# stm_v0_7.net
KiCad netlist of a schematic drawn in EAGLE
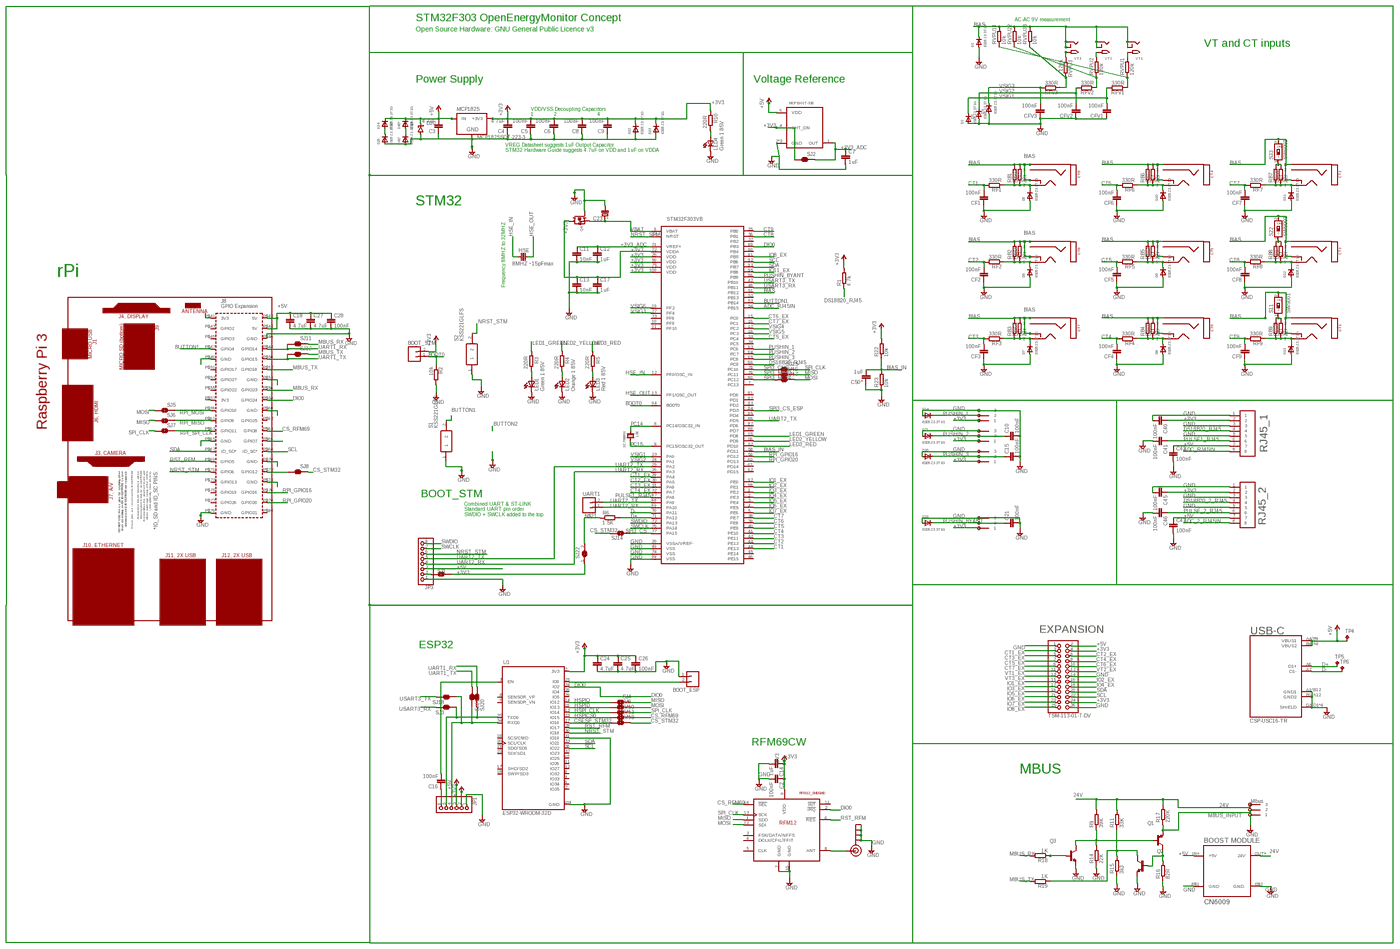
[diagram p0: schematic, sheet 1, overview]
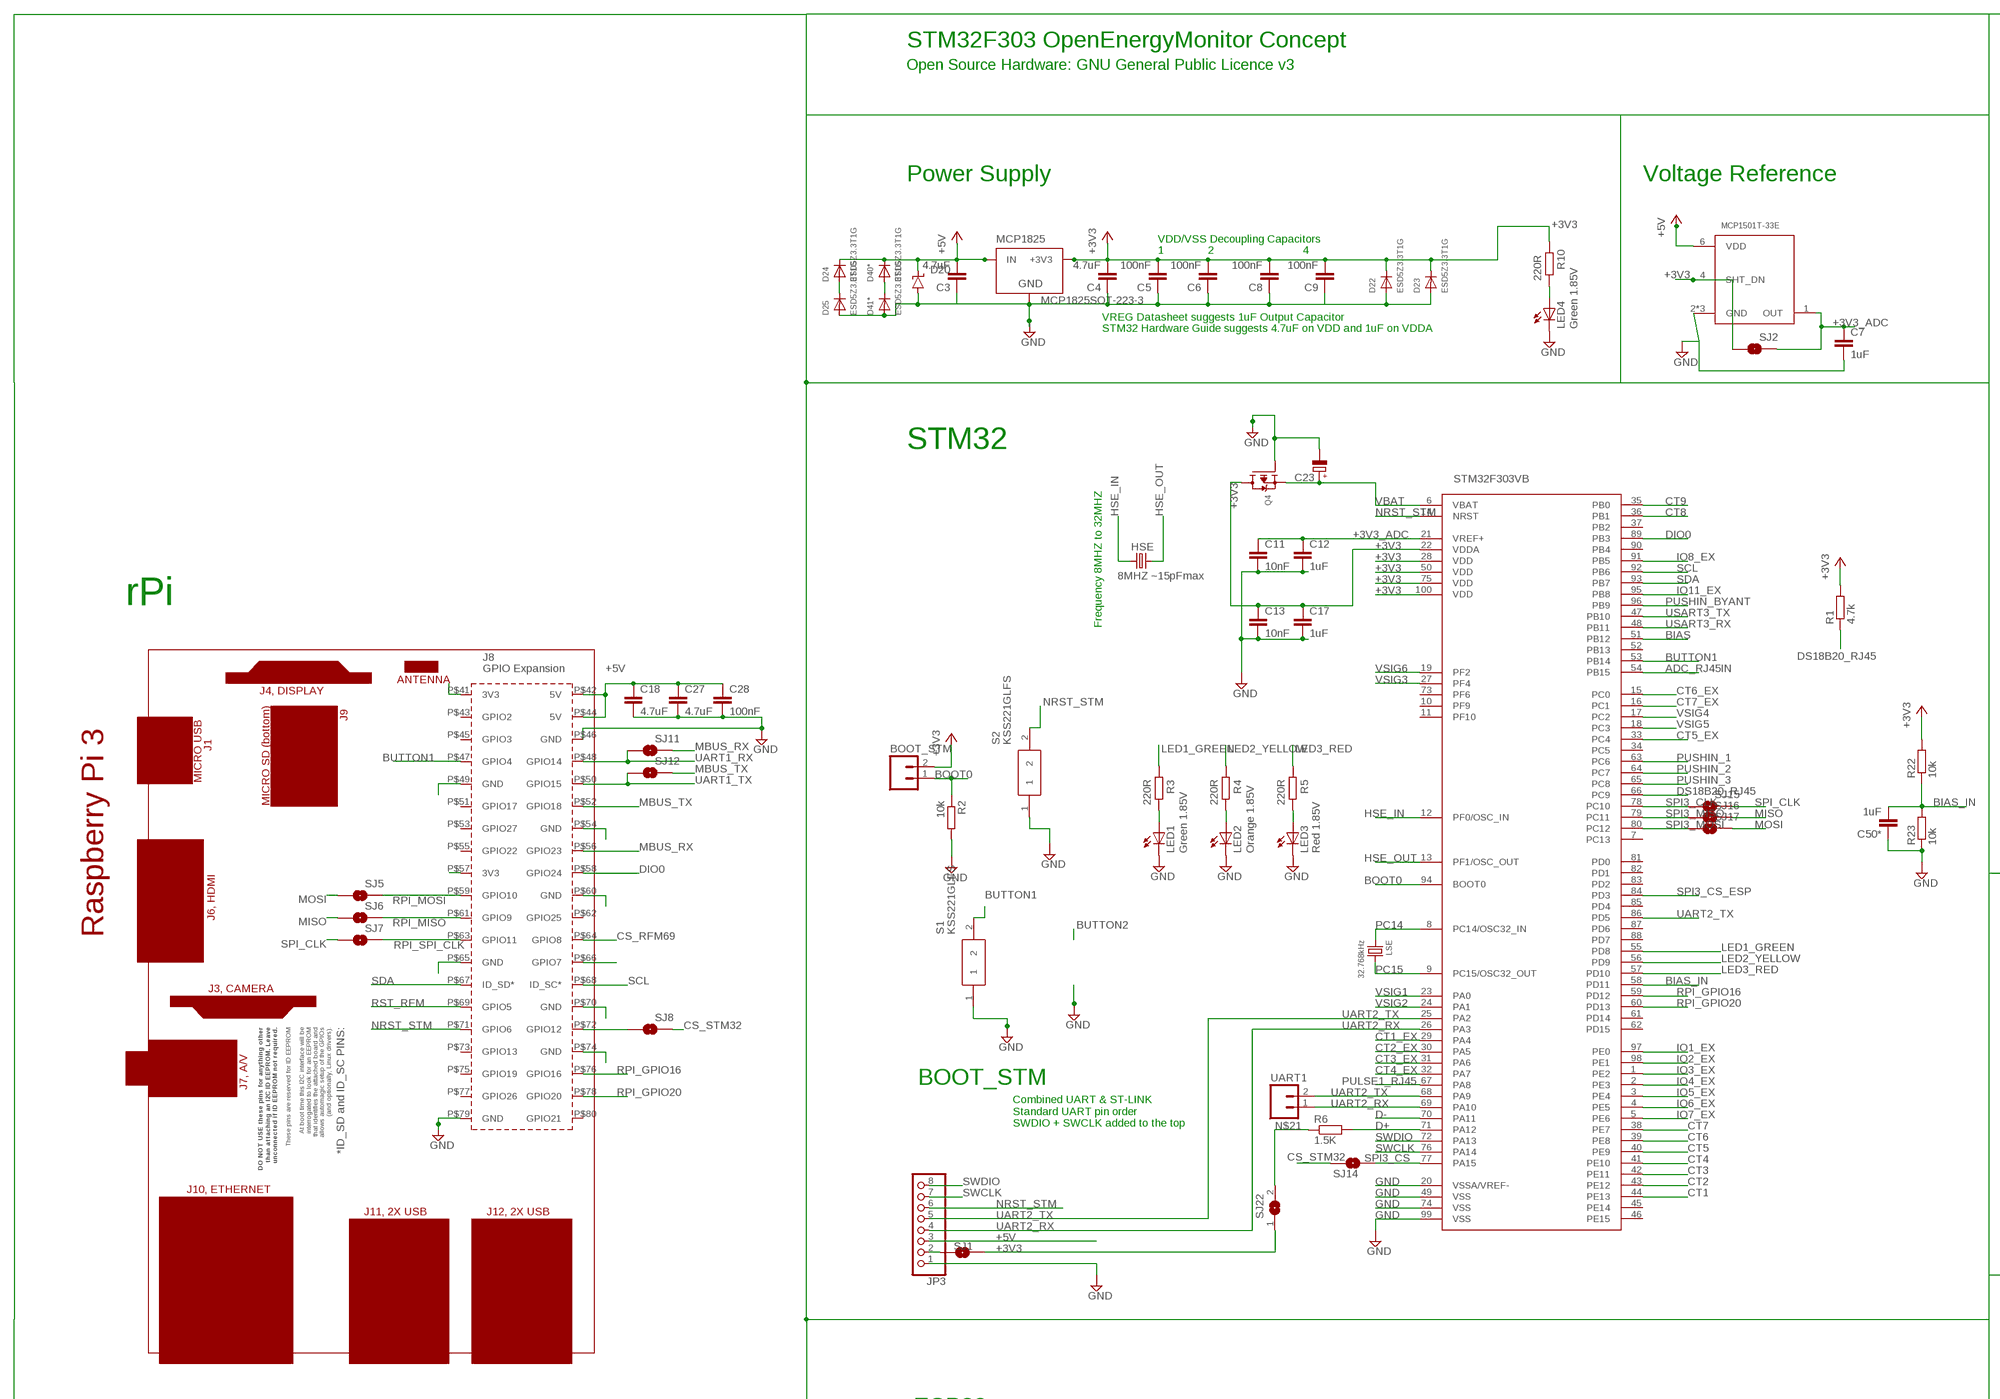
[diagram p1: schematic, sheet 1, part 1 of 4]
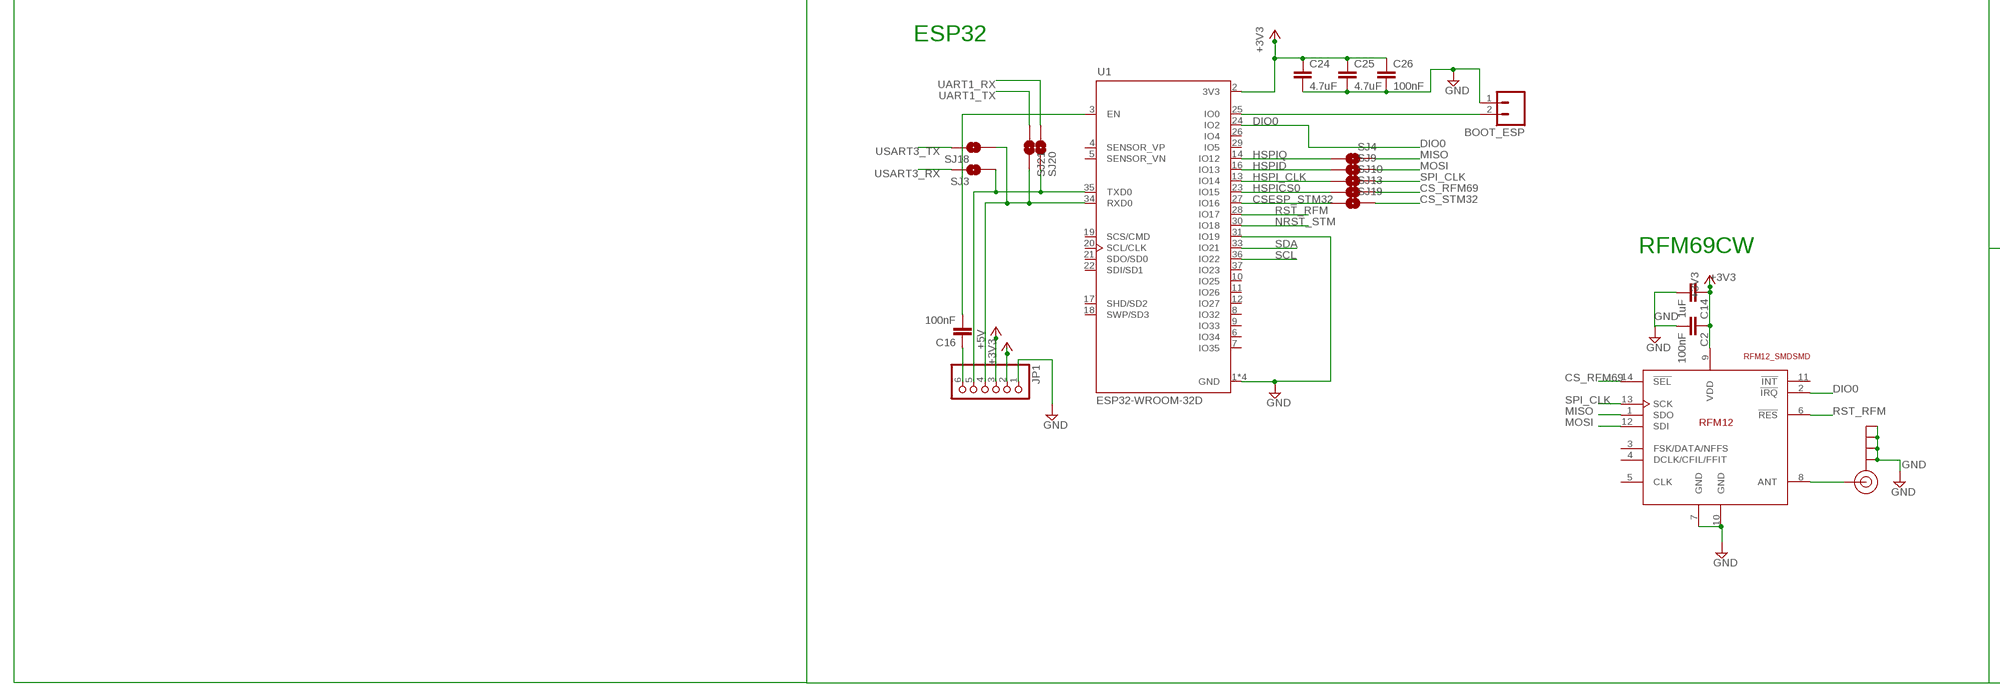
[diagram p2: schematic, sheet 1, part 2 of 4]
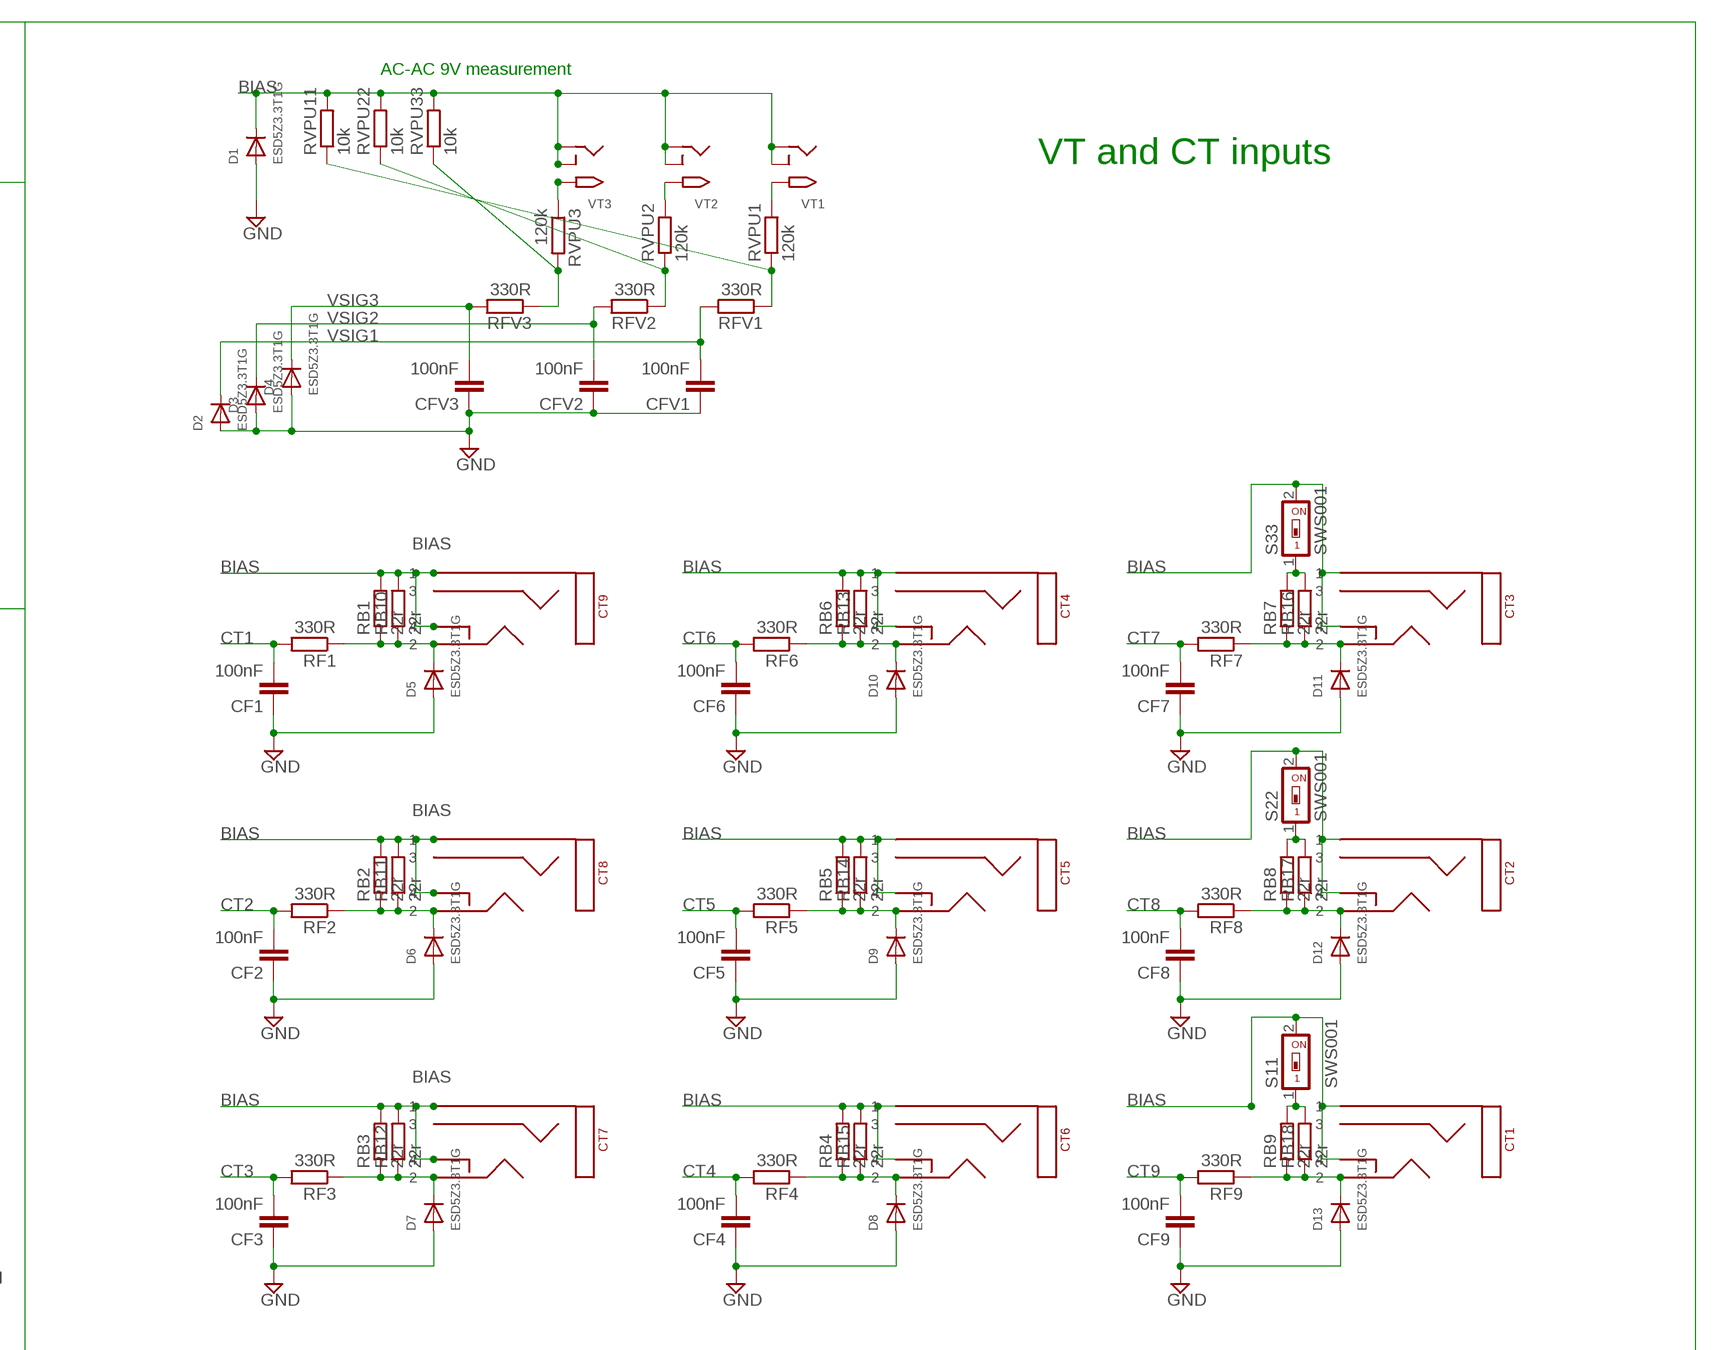
[diagram p3: schematic, sheet 1, part 3 of 4]
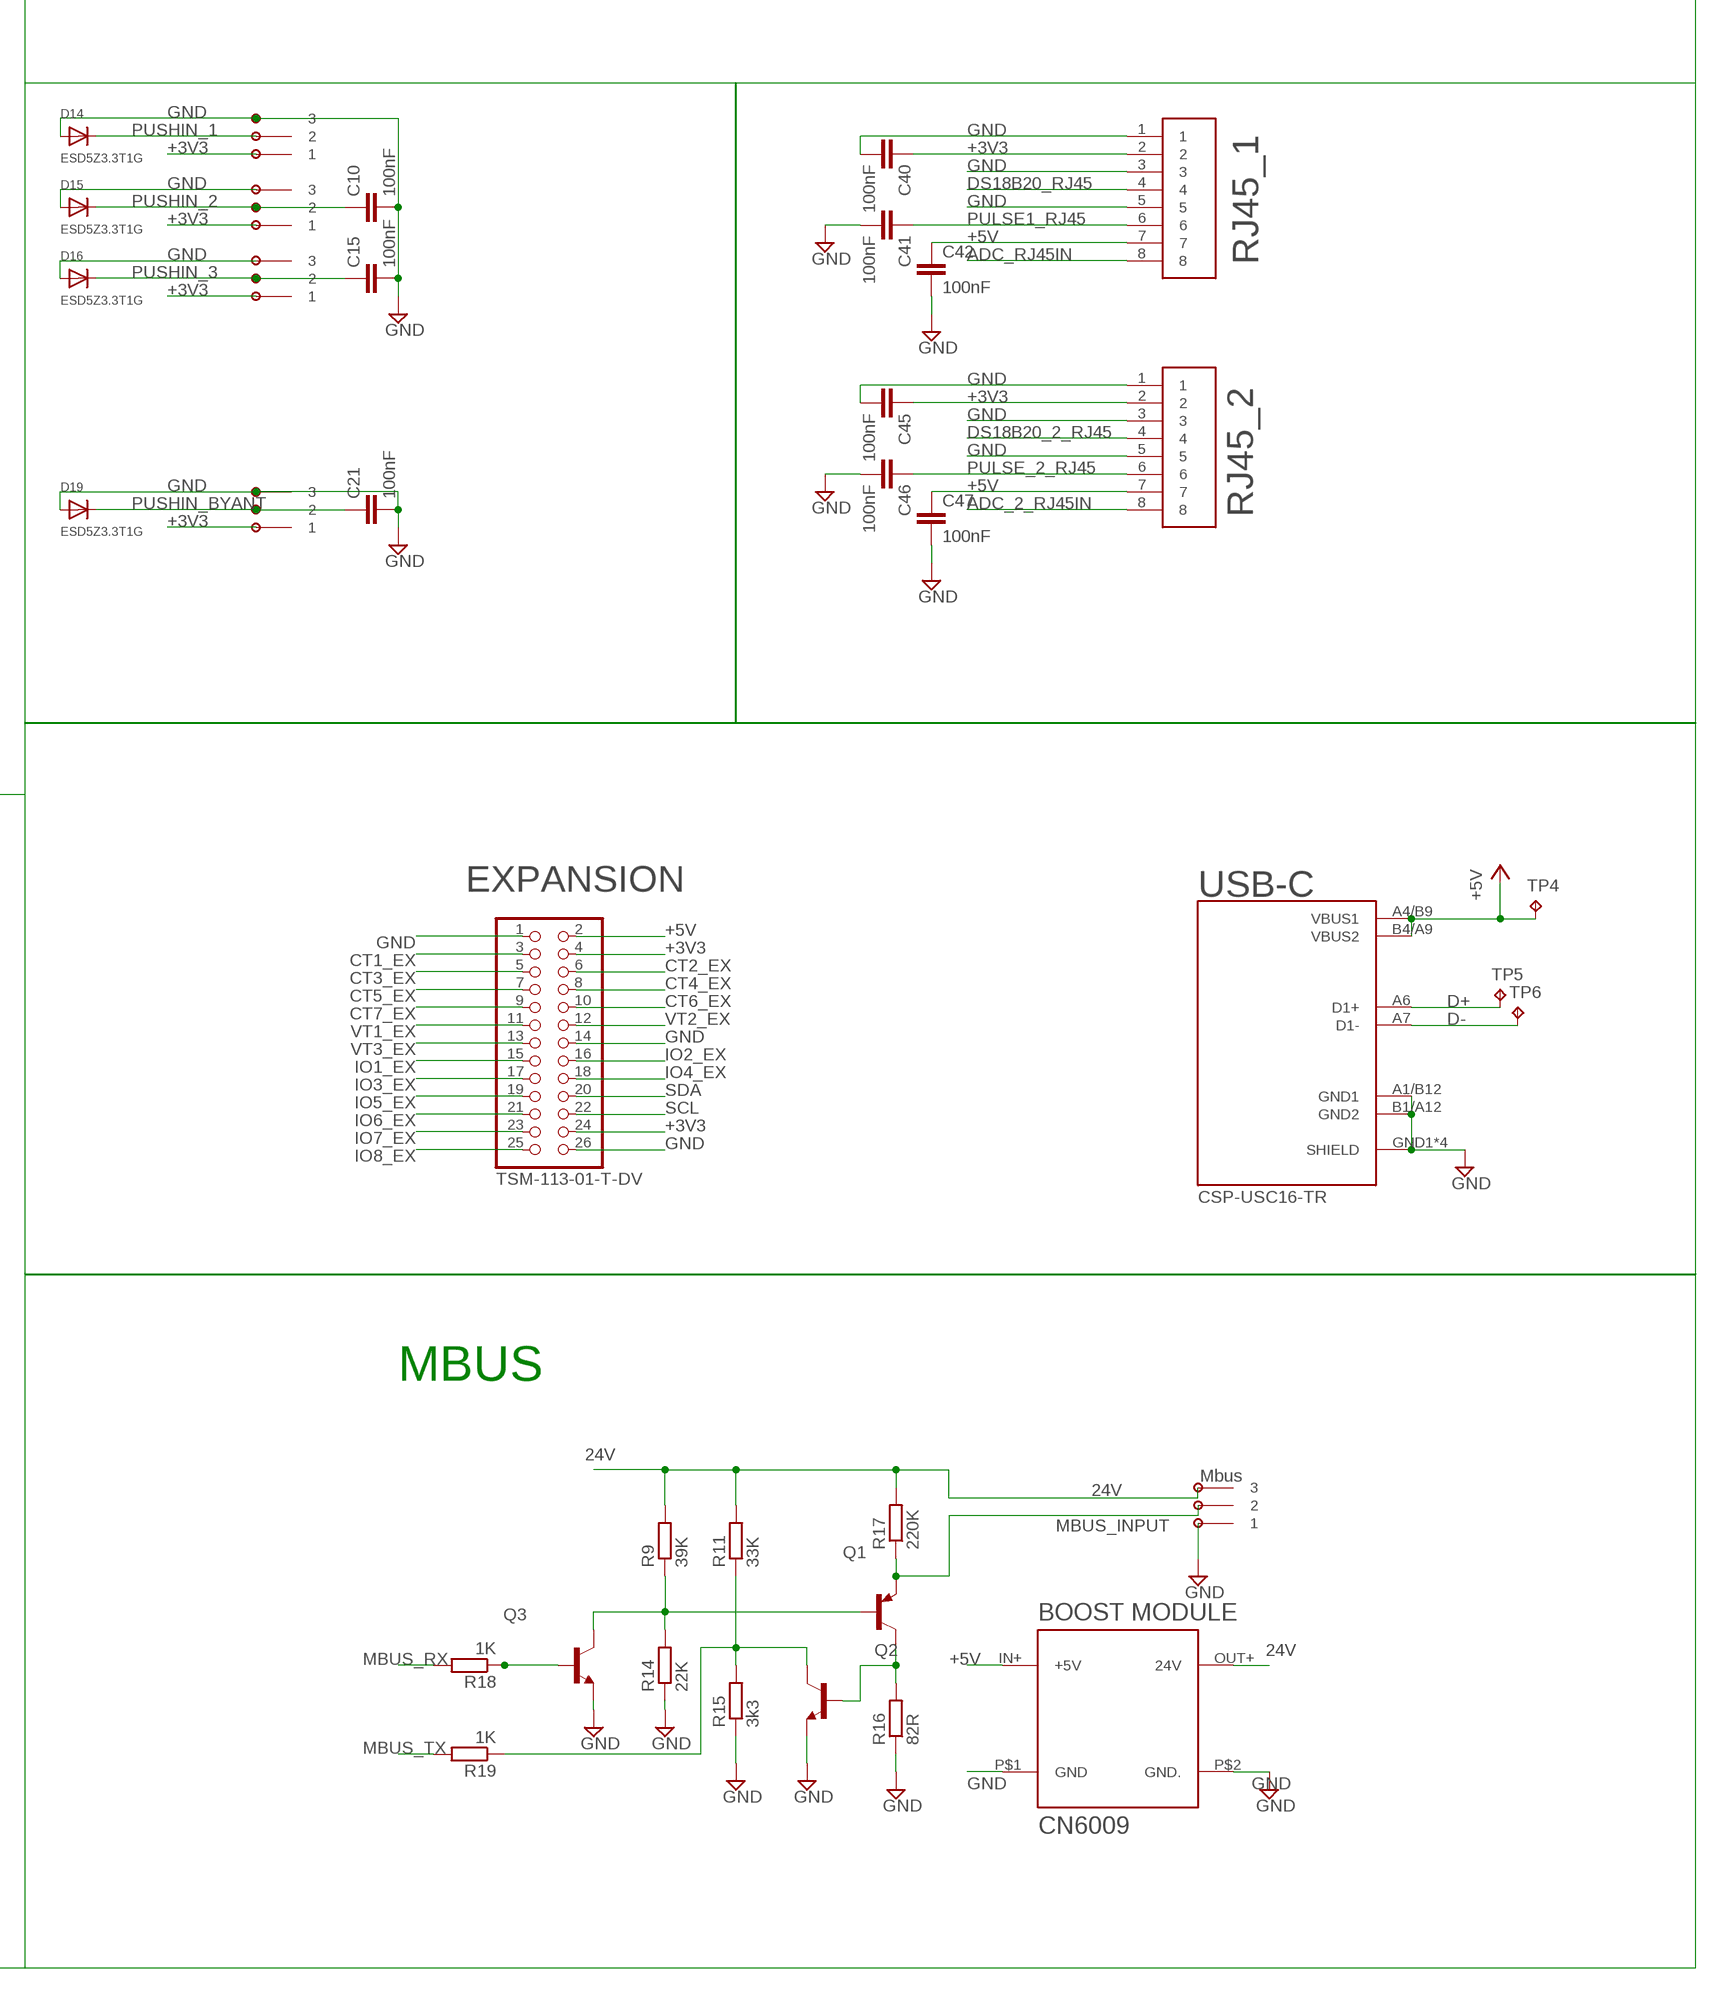
[diagram p4: schematic, sheet 1, part 4 of 4]

(export (version "E")
  (design (tool "Eeschema 10.0.6"))
  (components
    (comp (ref "3POLE_1")
      (value "OMNIMATE_LSF_3COMBICON_SMT_3")
      (footprint "eagle-import:OMNIMATE_LSF_3_SMT")
      (libsource (lib "eagle-import") (part "OMNIMATE_LSF_3COMBICON_SMT_3"))
    )
    (comp (ref "3POLE_2")
      (value "OMNIMATE_LSF_3COMBICON_SMT_3")
      (footprint "eagle-import:OMNIMATE_LSF_3_SMT")
      (libsource (lib "eagle-import") (part "OMNIMATE_LSF_3COMBICON_SMT_3"))
    )
    (comp (ref "3POLE_3")
      (value "OMNIMATE_LSF_3COMBICON_SMT_3")
      (footprint "eagle-import:OMNIMATE_LSF_3_SMT")
      (libsource (lib "eagle-import") (part "OMNIMATE_LSF_3COMBICON_SMT_3"))
    )
    (comp (ref "3POLE_6")
      (value "OMNIMATE_LSF_3COMBICON_SMT_3")
      (footprint "eagle-import:OMNIMATE_LSF_3_SMT")
      (libsource (lib "eagle-import") (part "OMNIMATE_LSF_3COMBICON_SMT_3"))
    )
    (comp (ref "3POLE_7")
      (value "OMNIMATE_LSF_3COMBICON_SMT_3")
      (footprint "eagle-import:OMNIMATE_LSF_3_SMT")
      (libsource (lib "eagle-import") (part "OMNIMATE_LSF_3COMBICON_SMT_3"))
    )
    (comp (ref "BOOT_ESP")
      (value "M02PTH")
      (footprint "eagle-import:1X02")
      (libsource (lib "eagle-import") (part "M02PTH"))
    )
    (comp (ref "BOOT_STM")
      (value "M02PTH")
      (footprint "eagle-import:1X02")
      (libsource (lib "eagle-import") (part "M02PTH"))
    )
    (comp (ref "C2")
      (value "100nF")
      (footprint "eagle-import:C0603")
      (libsource (lib "eagle-import") (part "resistor_C-EUC0603"))
    )
    (comp (ref "C3")
      (value "4.7uF")
      (footprint "eagle-import:C0805")
      (libsource (lib "eagle-import") (part "C-EUC0805"))
    )
    (comp (ref "C4")
      (value "4.7uF")
      (footprint "eagle-import:C0805")
      (libsource (lib "eagle-import") (part "C-EUC0805"))
    )
    (comp (ref "C5")
      (value "100nF")
      (footprint "eagle-import:C0603")
      (libsource (lib "eagle-import") (part "resistor_C-EUC0603"))
    )
    (comp (ref "C6")
      (value "100nF")
      (footprint "eagle-import:C0603")
      (libsource (lib "eagle-import") (part "resistor_C-EUC0603"))
    )
    (comp (ref "C7")
      (value "1uF")
      (footprint "eagle-import:C0805")
      (libsource (lib "eagle-import") (part "C-EUC0805"))
    )
    (comp (ref "C8")
      (value "100nF")
      (footprint "eagle-import:C0603")
      (libsource (lib "eagle-import") (part "resistor_C-EUC0603"))
    )
    (comp (ref "C9")
      (value "100nF")
      (footprint "eagle-import:C0603")
      (libsource (lib "eagle-import") (part "resistor_C-EUC0603"))
    )
    (comp (ref "C10")
      (value "100nF")
      (footprint "eagle-import:C0603")
      (libsource (lib "eagle-import") (part "resistor_C-EUC0603"))
    )
    (comp (ref "C11")
      (value "10nF")
      (footprint "eagle-import:C0603")
      (libsource (lib "eagle-import") (part "C-EUC0603"))
    )
    (comp (ref "C12")
      (value "1uF")
      (footprint "eagle-import:C0805")
      (libsource (lib "eagle-import") (part "C-EUC0805"))
    )
    (comp (ref "C13")
      (value "10nF")
      (footprint "eagle-import:C0603")
      (libsource (lib "eagle-import") (part "C-EUC0603"))
    )
    (comp (ref "C14")
      (value "1uF")
      (footprint "eagle-import:C0805")
      (libsource (lib "eagle-import") (part "C-EUC0805"))
    )
    (comp (ref "C15")
      (value "100nF")
      (footprint "eagle-import:C0603")
      (libsource (lib "eagle-import") (part "resistor_C-EUC0603"))
    )
    (comp (ref "C16")
      (value "100nF")
      (footprint "eagle-import:C0603")
      (libsource (lib "eagle-import") (part "resistor_C-EUC0603"))
    )
    (comp (ref "C17")
      (value "1uF")
      (footprint "eagle-import:C0805")
      (libsource (lib "eagle-import") (part "C-EUC0805"))
    )
    (comp (ref "C18")
      (value "4.7uF")
      (footprint "eagle-import:C0805")
      (libsource (lib "eagle-import") (part "C-EUC0805"))
    )
    (comp (ref "C21")
      (value "100nF")
      (footprint "eagle-import:C0603")
      (libsource (lib "eagle-import") (part "resistor_C-EUC0603"))
    )
    (comp (ref "C23")
      (value "CPOL-EU153CLV-1010")
      (footprint "eagle-import:153CLV-1010")
      (libsource (lib "eagle-import") (part "CPOL-EU153CLV-1010"))
    )
    (comp (ref "C24")
      (value "4.7uF")
      (footprint "eagle-import:C0805")
      (libsource (lib "eagle-import") (part "C-EUC0805"))
    )
    (comp (ref "C25")
      (value "4.7uF")
      (footprint "eagle-import:C0805")
      (libsource (lib "eagle-import") (part "C-EUC0805"))
    )
    (comp (ref "C26")
      (value "100nF")
      (footprint "eagle-import:C0603")
      (libsource (lib "eagle-import") (part "resistor_C-EUC0603"))
    )
    (comp (ref "C27")
      (value "4.7uF")
      (footprint "eagle-import:C0805")
      (libsource (lib "eagle-import") (part "C-EUC0805"))
    )
    (comp (ref "C28")
      (value "100nF")
      (footprint "eagle-import:C0603")
      (libsource (lib "eagle-import") (part "resistor_C-EUC0603"))
    )
    (comp (ref "C40")
      (value "100nF")
      (footprint "eagle-import:C0603")
      (libsource (lib "eagle-import") (part "resistor_C-EUC0603"))
    )
    (comp (ref "C41")
      (value "100nF")
      (footprint "eagle-import:C0603")
      (libsource (lib "eagle-import") (part "resistor_C-EUC0603"))
    )
    (comp (ref "C42")
      (value "100nF")
      (footprint "eagle-import:C0603")
      (libsource (lib "eagle-import") (part "resistor_C-EUC0603"))
    )
    (comp (ref "C45")
      (value "100nF")
      (footprint "eagle-import:C0603")
      (libsource (lib "eagle-import") (part "resistor_C-EUC0603"))
    )
    (comp (ref "C46")
      (value "100nF")
      (footprint "eagle-import:C0603")
      (libsource (lib "eagle-import") (part "resistor_C-EUC0603"))
    )
    (comp (ref "C47")
      (value "100nF")
      (footprint "eagle-import:C0603")
      (libsource (lib "eagle-import") (part "resistor_C-EUC0603"))
    )
    (comp (ref "C50*")
      (value "1uF")
      (footprint "eagle-import:C0603")
      (libsource (lib "eagle-import") (part "C-EUC0603"))
    )
    (comp (ref "CF1")
      (value "100nF")
      (footprint "eagle-import:C0603")
      (libsource (lib "eagle-import") (part "resistor_C-EUC0603"))
    )
    (comp (ref "CF2")
      (value "100nF")
      (footprint "eagle-import:C0603")
      (libsource (lib "eagle-import") (part "resistor_C-EUC0603"))
    )
    (comp (ref "CF3")
      (value "100nF")
      (footprint "eagle-import:C0603")
      (libsource (lib "eagle-import") (part "resistor_C-EUC0603"))
    )
    (comp (ref "CF4")
      (value "100nF")
      (footprint "eagle-import:C0603")
      (libsource (lib "eagle-import") (part "resistor_C-EUC0603"))
    )
    (comp (ref "CF5")
      (value "100nF")
      (footprint "eagle-import:C0603")
      (libsource (lib "eagle-import") (part "resistor_C-EUC0603"))
    )
    (comp (ref "CF6")
      (value "100nF")
      (footprint "eagle-import:C0603")
      (libsource (lib "eagle-import") (part "resistor_C-EUC0603"))
    )
    (comp (ref "CF7")
      (value "100nF")
      (footprint "eagle-import:C0603")
      (libsource (lib "eagle-import") (part "resistor_C-EUC0603"))
    )
    (comp (ref "CF8")
      (value "100nF")
      (footprint "eagle-import:C0603")
      (libsource (lib "eagle-import") (part "resistor_C-EUC0603"))
    )
    (comp (ref "CF9")
      (value "100nF")
      (footprint "eagle-import:C0603")
      (libsource (lib "eagle-import") (part "resistor_C-EUC0603"))
    )
    (comp (ref "CFV1")
      (value "100nF")
      (footprint "eagle-import:C0603")
      (libsource (lib "eagle-import") (part "resistor_C-EUC0603"))
    )
    (comp (ref "CFV2")
      (value "100nF")
      (footprint "eagle-import:C0603")
      (libsource (lib "eagle-import") (part "resistor_C-EUC0603"))
    )
    (comp (ref "CFV3")
      (value "100nF")
      (footprint "eagle-import:C0603")
      (libsource (lib "eagle-import") (part "resistor_C-EUC0603"))
    )
    (comp (ref "CT1")
      (value "STEREO_SMD")
      (footprint "eagle-import:STEREO_SMT")
      (libsource (lib "eagle-import") (part "STEREO_SMD"))
    )
    (comp (ref "CT2")
      (value "STEREO_SMD")
      (footprint "eagle-import:STEREO_SMT")
      (libsource (lib "eagle-import") (part "STEREO_SMD"))
    )
    (comp (ref "CT3")
      (value "STEREO_SMD")
      (footprint "eagle-import:STEREO_SMT")
      (libsource (lib "eagle-import") (part "STEREO_SMD"))
    )
    (comp (ref "CT4")
      (value "STEREO_SMD")
      (footprint "eagle-import:STEREO_SMT")
      (libsource (lib "eagle-import") (part "STEREO_SMD"))
    )
    (comp (ref "CT5")
      (value "STEREO_SMD")
      (footprint "eagle-import:STEREO_SMT")
      (libsource (lib "eagle-import") (part "STEREO_SMD"))
    )
    (comp (ref "CT6")
      (value "STEREO_SMD")
      (footprint "eagle-import:STEREO_SMT")
      (libsource (lib "eagle-import") (part "STEREO_SMD"))
    )
    (comp (ref "CT7")
      (value "STEREO_SMD")
      (footprint "eagle-import:STEREO_SMT")
      (libsource (lib "eagle-import") (part "STEREO_SMD"))
    )
    (comp (ref "CT8")
      (value "STEREO_SMD")
      (footprint "eagle-import:STEREO_SMT")
      (libsource (lib "eagle-import") (part "STEREO_SMD"))
    )
    (comp (ref "CT9")
      (value "STEREO_SMD")
      (footprint "eagle-import:STEREO_SMT")
      (libsource (lib "eagle-import") (part "STEREO_SMD"))
    )
    (comp (ref "D1")
      (value "ESD5Z3.3T1G")
      (footprint "eagle-import:SOD-523")
      (libsource (lib "eagle-import") (part "DIODESOD-523"))
    )
    (comp (ref "D2")
      (value "ESD5Z3.3T1G")
      (footprint "eagle-import:SOD-523")
      (libsource (lib "eagle-import") (part "DIODESOD-523"))
    )
    (comp (ref "D3")
      (value "ESD5Z3.3T1G")
      (footprint "eagle-import:SOD-523")
      (libsource (lib "eagle-import") (part "DIODESOD-523"))
    )
    (comp (ref "D4")
      (value "ESD5Z3.3T1G")
      (footprint "eagle-import:SOD-523")
      (libsource (lib "eagle-import") (part "DIODESOD-523"))
    )
    (comp (ref "D5")
      (value "ESD5Z3.3T1G")
      (footprint "eagle-import:SOD-523")
      (libsource (lib "eagle-import") (part "DIODESOD-523"))
    )
    (comp (ref "D6")
      (value "ESD5Z3.3T1G")
      (footprint "eagle-import:SOD-523")
      (libsource (lib "eagle-import") (part "DIODESOD-523"))
    )
    (comp (ref "D7")
      (value "ESD5Z3.3T1G")
      (footprint "eagle-import:SOD-523")
      (libsource (lib "eagle-import") (part "DIODESOD-523"))
    )
    (comp (ref "D8")
      (value "ESD5Z3.3T1G")
      (footprint "eagle-import:SOD-523")
      (libsource (lib "eagle-import") (part "DIODESOD-523"))
    )
    (comp (ref "D9")
      (value "ESD5Z3.3T1G")
      (footprint "eagle-import:SOD-523")
      (libsource (lib "eagle-import") (part "DIODESOD-523"))
    )
    (comp (ref "D10")
      (value "ESD5Z3.3T1G")
      (footprint "eagle-import:SOD-523")
      (libsource (lib "eagle-import") (part "DIODESOD-523"))
    )
    (comp (ref "D11")
      (value "ESD5Z3.3T1G")
      (footprint "eagle-import:SOD-523")
      (libsource (lib "eagle-import") (part "DIODESOD-523"))
    )
    (comp (ref "D12")
      (value "ESD5Z3.3T1G")
      (footprint "eagle-import:SOD-523")
      (libsource (lib "eagle-import") (part "DIODESOD-523"))
    )
    (comp (ref "D13")
      (value "ESD5Z3.3T1G")
      (footprint "eagle-import:SOD-523")
      (libsource (lib "eagle-import") (part "DIODESOD-523"))
    )
    (comp (ref "D14")
      (value "ESD5Z3.3T1G")
      (footprint "eagle-import:SOD-523")
      (libsource (lib "eagle-import") (part "DIODESOD-523"))
    )
    (comp (ref "D15")
      (value "ESD5Z3.3T1G")
      (footprint "eagle-import:SOD-523")
      (libsource (lib "eagle-import") (part "DIODESOD-523"))
    )
    (comp (ref "D16")
      (value "ESD5Z3.3T1G")
      (footprint "eagle-import:SOD-523")
      (libsource (lib "eagle-import") (part "DIODESOD-523"))
    )
    (comp (ref "D19")
      (value "ESD5Z3.3T1G")
      (footprint "eagle-import:SOD-523")
      (libsource (lib "eagle-import") (part "DIODESOD-523"))
    )
    (comp (ref "D20")
      (value "SUPPRESSOR-SMBJ")
      (footprint "eagle-import:SMBJ")
      (libsource (lib "eagle-import") (part "SUPPRESSOR-SMBJ"))
    )
    (comp (ref "D22")
      (value "ESD5Z3.3T1G")
      (footprint "eagle-import:SOD-523")
      (libsource (lib "eagle-import") (part "DIODESOD-523"))
    )
    (comp (ref "D23")
      (value "ESD5Z3.3T1G")
      (footprint "eagle-import:SOD-523")
      (libsource (lib "eagle-import") (part "DIODESOD-523"))
    )
    (comp (ref "D24")
      (value "ESD5Z3.3T1G")
      (footprint "eagle-import:SOD-523")
      (libsource (lib "eagle-import") (part "DIODESOD-523"))
    )
    (comp (ref "D25")
      (value "ESD5Z3.3T1G")
      (footprint "eagle-import:SOD-523")
      (libsource (lib "eagle-import") (part "DIODESOD-523"))
    )
    (comp (ref "D40*")
      (value "ESD5Z3.3T1G")
      (footprint "eagle-import:SOD-523")
      (libsource (lib "eagle-import") (part "DIODESOD-523"))
    )
    (comp (ref "D41*")
      (value "ESD5Z3.3T1G")
      (footprint "eagle-import:SOD-523")
      (libsource (lib "eagle-import") (part "DIODESOD-523"))
    )
    (comp (ref "EXPANSION")
      (value "TSM-113-01-T-DV")
      (footprint "eagle-import:2X13_SMT")
      (libsource (lib "eagle-import") (part "PINHD-2X13SMT"))
    )
    (comp (ref "HSE")
      (value "8MHZ ~15pFmax")
      (footprint "eagle-import:CTS406")
      (libsource (lib "eagle-import") (part "CRYSTALCTS406"))
    )
    (comp (ref "J$1")
      (value "SMA_EDGE")
      (footprint "eagle-import:SMA-EDGE")
      (libsource (lib "eagle-import") (part "SMA_EDGE"))
    )
    (comp (ref "JP1")
      (value "PINHD-1X61X06_SMT")
      (footprint "eagle-import:1X06_SMT")
      (libsource (lib "eagle-import") (part "PINHD-1X61X06_SMT"))
    )
    (comp (ref "JP3")
      (value "PINHD-1X81X08_SMT")
      (footprint "eagle-import:1X08_SMT")
      (libsource (lib "eagle-import") (part "PINHD-1X81X08_SMT"))
    )
    (comp (ref "LED1")
      (value "Green 1.85V")
      (footprint "eagle-import:CHIP-LED0805")
      (libsource (lib "eagle-import") (part "LEDCHIP-LED0805"))
    )
    (comp (ref "LED2")
      (value "Orange 1.85V")
      (footprint "eagle-import:CHIP-LED0805")
      (libsource (lib "eagle-import") (part "LEDCHIP-LED0805"))
    )
    (comp (ref "LED3")
      (value "Red 1.85V")
      (footprint "eagle-import:CHIP-LED0805")
      (libsource (lib "eagle-import") (part "LEDCHIP-LED0805"))
    )
    (comp (ref "LED4")
      (value "Green 1.85V")
      (footprint "eagle-import:CHIP-LED0805")
      (libsource (lib "eagle-import") (part "LEDCHIP-LED0805"))
    )
    (comp (ref "LSE")
      (value "32.768kHz")
      (footprint "eagle-import:CRYSTAL_8X3.8")
      (libsource (lib "eagle-import") (part "CRYSTAL8X3.8SMT"))
    )
    (comp (ref "MCP1825")
      (value "MCP1825SOT-223-3")
      (footprint "eagle-import:SOT-223")
      (libsource (lib "eagle-import") (part "MCP1825SOT-223-3"))
    )
    (comp (ref "PCB2")
      (value "RPI3YA")
      (footprint "eagle-import:RPI3MIRROR2")
      (libsource (lib "eagle-import") (part "RPI3YA"))
    )
    (comp (ref "Q1")
      (value "MMBT3906")
      (footprint "eagle-import:SOT23")
      (fields
        (field (name "DIGIKEY_PART_NUMBER") "MMBT3906FSCT-ND")
        (field (name "MANUFACTURER") "ON Semiconductor")
        (field (name "CREATED_BY") "PCB Layout")
      )
      (libsource (lib "eagle-import") (part "MMBT3906"))
    )
    (comp (ref "Q2")
      (value "MMBT3904")
      (footprint "eagle-import:SOT23")
      (fields
        (field (name "DIGIKEY_PART_NUMBER") "MMBT3904FSCT-ND")
        (field (name "MANUFACTURER") "ON Semiconductor")
        (field (name "CREATED_BY") "PCB Layout")
      )
      (libsource (lib "eagle-import") (part "MMBT3904"))
    )
    (comp (ref "Q3")
      (value "MMBT3904")
      (footprint "eagle-import:SOT23")
      (fields
        (field (name "DIGIKEY_PART_NUMBER") "MMBT3904FSCT-ND")
        (field (name "MANUFACTURER") "ON Semiconductor")
        (field (name "CREATED_BY") "PCB Layout")
      )
      (libsource (lib "eagle-import") (part "MMBT3904"))
    )
    (comp (ref "Q4")
      (value "MOSFET-P")
      (footprint "eagle-import:SOT23-R")
      (libsource (lib "eagle-import") (part "MOSFET-P"))
    )
    (comp (ref "R1")
      (value "4.7k")
      (footprint "eagle-import:R0603")
      (libsource (lib "eagle-import") (part "resistor_R-EU_R0603"))
    )
    (comp (ref "R2")
      (value "10k")
      (footprint "eagle-import:R0603")
      (libsource (lib "eagle-import") (part "resistor_R-EU_R0603"))
    )
    (comp (ref "R3")
      (value "220R")
      (footprint "eagle-import:R0603")
      (libsource (lib "eagle-import") (part "R-EU_R0603"))
    )
    (comp (ref "R4")
      (value "220R")
      (footprint "eagle-import:R0603")
      (libsource (lib "eagle-import") (part "R-EU_R0603"))
    )
    (comp (ref "R5")
      (value "220R")
      (footprint "eagle-import:R0603")
      (libsource (lib "eagle-import") (part "R-EU_R0603"))
    )
    (comp (ref "R6")
      (value "1.5K")
      (footprint "eagle-import:R0603")
      (libsource (lib "eagle-import") (part "R-EU_R0603"))
    )
    (comp (ref "R9")
      (value "39K")
      (footprint "eagle-import:R0603")
      (libsource (lib "eagle-import") (part "R-EU_R0603"))
    )
    (comp (ref "R10")
      (value "220R")
      (footprint "eagle-import:R0603")
      (libsource (lib "eagle-import") (part "R-EU_R0603"))
    )
    (comp (ref "R11")
      (value "33K")
      (footprint "eagle-import:R0603")
      (libsource (lib "eagle-import") (part "R-EU_R0603"))
    )
    (comp (ref "R14")
      (value "22K")
      (footprint "eagle-import:R0603")
      (libsource (lib "eagle-import") (part "R-EU_R0603"))
    )
    (comp (ref "R15")
      (value "3k3")
      (footprint "eagle-import:R0603")
      (libsource (lib "eagle-import") (part "R-EU_R0603"))
    )
    (comp (ref "R16")
      (value "82R")
      (footprint "eagle-import:R0603")
      (libsource (lib "eagle-import") (part "R-EU_R0603"))
    )
    (comp (ref "R17")
      (value "220K")
      (footprint "eagle-import:R0603")
      (libsource (lib "eagle-import") (part "R-EU_R0603"))
    )
    (comp (ref "R18")
      (value "1K")
      (footprint "eagle-import:R0603")
      (libsource (lib "eagle-import") (part "R-EU_R0603"))
    )
    (comp (ref "R19")
      (value "1K")
      (footprint "eagle-import:R0603")
      (libsource (lib "eagle-import") (part "R-EU_R0603"))
    )
    (comp (ref "R22")
      (value "10k")
      (footprint "eagle-import:R0603")
      (libsource (lib "eagle-import") (part "resistor_R-EU_R0603"))
    )
    (comp (ref "R23")
      (value "10k")
      (footprint "eagle-import:R0603")
      (libsource (lib "eagle-import") (part "resistor_R-EU_R0603"))
    )
    (comp (ref "RB1")
      (value "22r")
      (footprint "eagle-import:R0603")
      (libsource (lib "eagle-import") (part "resistor_R-EU_R0603"))
    )
    (comp (ref "RB2")
      (value "22r")
      (footprint "eagle-import:R0603")
      (libsource (lib "eagle-import") (part "resistor_R-EU_R0603"))
    )
    (comp (ref "RB3")
      (value "22r")
      (footprint "eagle-import:R0603")
      (libsource (lib "eagle-import") (part "resistor_R-EU_R0603"))
    )
    (comp (ref "RB4")
      (value "22r")
      (footprint "eagle-import:R0603")
      (libsource (lib "eagle-import") (part "resistor_R-EU_R0603"))
    )
    (comp (ref "RB5")
      (value "22r")
      (footprint "eagle-import:R0603")
      (libsource (lib "eagle-import") (part "resistor_R-EU_R0603"))
    )
    (comp (ref "RB6")
      (value "22r")
      (footprint "eagle-import:R0603")
      (libsource (lib "eagle-import") (part "resistor_R-EU_R0603"))
    )
    (comp (ref "RB7")
      (value "22r")
      (footprint "eagle-import:R0603")
      (libsource (lib "eagle-import") (part "resistor_R-EU_R0603"))
    )
    (comp (ref "RB8")
      (value "22r")
      (footprint "eagle-import:R0603")
      (libsource (lib "eagle-import") (part "resistor_R-EU_R0603"))
    )
    (comp (ref "RB9")
      (value "22r")
      (footprint "eagle-import:R0603")
      (libsource (lib "eagle-import") (part "resistor_R-EU_R0603"))
    )
    (comp (ref "RB10")
      (value "22r")
      (footprint "eagle-import:0207_7")
      (libsource (lib "eagle-import") (part "R-EU_0207/7"))
    )
    (comp (ref "RB11")
      (value "22r")
      (footprint "eagle-import:0207_7")
      (libsource (lib "eagle-import") (part "R-EU_0207/7"))
    )
    (comp (ref "RB12")
      (value "22r")
      (footprint "eagle-import:0207_7")
      (libsource (lib "eagle-import") (part "R-EU_0207/7"))
    )
    (comp (ref "RB13")
      (value "22r")
      (footprint "eagle-import:0207_7")
      (libsource (lib "eagle-import") (part "R-EU_0207/7"))
    )
    (comp (ref "RB14")
      (value "22r")
      (footprint "eagle-import:0207_7")
      (libsource (lib "eagle-import") (part "R-EU_0207/7"))
    )
    (comp (ref "RB15")
      (value "22r")
      (footprint "eagle-import:0207_7")
      (libsource (lib "eagle-import") (part "R-EU_0207/7"))
    )
    (comp (ref "RB16")
      (value "22r")
      (footprint "eagle-import:0207_7")
      (libsource (lib "eagle-import") (part "R-EU_0207/7"))
    )
    (comp (ref "RB17")
      (value "22r")
      (footprint "eagle-import:0207_7")
      (libsource (lib "eagle-import") (part "R-EU_0207/7"))
    )
    (comp (ref "RB18")
      (value "22r")
      (footprint "eagle-import:0207_7")
      (libsource (lib "eagle-import") (part "R-EU_0207/7"))
    )
    (comp (ref "RF1")
      (value "330R")
      (footprint "eagle-import:R0603")
      (libsource (lib "eagle-import") (part "resistor_R-EU_R0603"))
    )
    (comp (ref "RF2")
      (value "330R")
      (footprint "eagle-import:R0603")
      (libsource (lib "eagle-import") (part "resistor_R-EU_R0603"))
    )
    (comp (ref "RF3")
      (value "330R")
      (footprint "eagle-import:R0603")
      (libsource (lib "eagle-import") (part "resistor_R-EU_R0603"))
    )
    (comp (ref "RF4")
      (value "330R")
      (footprint "eagle-import:R0603")
      (libsource (lib "eagle-import") (part "resistor_R-EU_R0603"))
    )
    (comp (ref "RF5")
      (value "330R")
      (footprint "eagle-import:R0603")
      (libsource (lib "eagle-import") (part "resistor_R-EU_R0603"))
    )
    (comp (ref "RF6")
      (value "330R")
      (footprint "eagle-import:R0603")
      (libsource (lib "eagle-import") (part "resistor_R-EU_R0603"))
    )
    (comp (ref "RF7")
      (value "330R")
      (footprint "eagle-import:R0603")
      (libsource (lib "eagle-import") (part "resistor_R-EU_R0603"))
    )
    (comp (ref "RF8")
      (value "330R")
      (footprint "eagle-import:R0603")
      (libsource (lib "eagle-import") (part "resistor_R-EU_R0603"))
    )
    (comp (ref "RF9")
      (value "330R")
      (footprint "eagle-import:R0603")
      (libsource (lib "eagle-import") (part "resistor_R-EU_R0603"))
    )
    (comp (ref "RFM69HCW")
      (value "RFM12_SMDSMD")
      (footprint "eagle-import:RFM12")
      (libsource (lib "eagle-import") (part "RFM12_SMDSMD"))
    )
    (comp (ref "RFV1")
      (value "330R")
      (footprint "eagle-import:R0603")
      (libsource (lib "eagle-import") (part "resistor_R-EU_R0603"))
    )
    (comp (ref "RFV2")
      (value "330R")
      (footprint "eagle-import:R0603")
      (libsource (lib "eagle-import") (part "resistor_R-EU_R0603"))
    )
    (comp (ref "RFV3")
      (value "330R")
      (footprint "eagle-import:R0603")
      (libsource (lib "eagle-import") (part "resistor_R-EU_R0603"))
    )
    (comp (ref "RJ45_1")
      (value "95501-6889")
      (footprint "eagle-import:955016889")
      (fields (field (name "MOUSER_PART_NUMBER") "538-95501-6889") (field (name "RS_PART_NUMBER") "3862738"))
      (libsource (lib "eagle-import") (part "95501-6889"))
    )
    (comp (ref "RJ45_2")
      (value "95501-6889")
      (footprint "eagle-import:955016889")
      (fields (field (name "MOUSER_PART_NUMBER") "538-95501-6889") (field (name "RS_PART_NUMBER") "3862738"))
      (libsource (lib "eagle-import") (part "95501-6889"))
    )
    (comp (ref "RVPU1")
      (value "120k")
      (footprint "eagle-import:R0603")
      (libsource (lib "eagle-import") (part "resistor_R-EU_R0603"))
    )
    (comp (ref "RVPU2")
      (value "120k")
      (footprint "eagle-import:R0603")
      (libsource (lib "eagle-import") (part "resistor_R-EU_R0603"))
    )
    (comp (ref "RVPU3")
      (value "120k")
      (footprint "eagle-import:R0603")
      (libsource (lib "eagle-import") (part "resistor_R-EU_R0603"))
    )
    (comp (ref "RVPU11")
      (value "10k")
      (footprint "eagle-import:R0603")
      (libsource (lib "eagle-import") (part "resistor_R-EU_R0603"))
    )
    (comp (ref "RVPU22")
      (value "10k")
      (footprint "eagle-import:R0603")
      (libsource (lib "eagle-import") (part "resistor_R-EU_R0603"))
    )
    (comp (ref "RVPU33")
      (value "10k")
      (footprint "eagle-import:R0603")
      (libsource (lib "eagle-import") (part "resistor_R-EU_R0603"))
    )
    (comp (ref "S1")
      (value "KSS221GLFS")
      (footprint "eagle-import:KSS")
      (fields (field (name "RS_PART_NUMBER") "7931689P"))
      (libsource (lib "eagle-import") (part "KSS221GLFS"))
    )
    (comp (ref "S2")
      (value "KSS221GLFS")
      (footprint "eagle-import:KSS")
      (fields (field (name "RS_PART_NUMBER") "7931689P"))
      (libsource (lib "eagle-import") (part "KSS221GLFS"))
    )
    (comp (ref "S11")
      (value "SWS001")
      (footprint "eagle-import:SMS-001")
      (libsource (lib "eagle-import") (part "SWS001"))
    )
    (comp (ref "S22")
      (value "SWS001")
      (footprint "eagle-import:SMS-001")
      (libsource (lib "eagle-import") (part "SWS001"))
    )
    (comp (ref "S33")
      (value "SWS001")
      (footprint "eagle-import:SMS-001")
      (libsource (lib "eagle-import") (part "SWS001"))
    )
    (comp (ref "SJ1")
      (value "SOLDERJUMPERNO")
      (footprint "eagle-import:SJ_2S-NO")
      (libsource (lib "eagle-import") (part "SOLDERJUMPERNO"))
    )
    (comp (ref "SJ2")
      (value "SOLDERJUMPERNO")
      (footprint "eagle-import:SJ_2S-NO")
      (libsource (lib "eagle-import") (part "SOLDERJUMPERNO"))
    )
    (comp (ref "SJ3")
      (value "SOLDERJUMPERNO")
      (footprint "eagle-import:SJ_2S-NO")
      (libsource (lib "eagle-import") (part "SOLDERJUMPERNO"))
    )
    (comp (ref "SJ4")
      (value "SOLDERJUMPERNO")
      (footprint "eagle-import:SJ_2S-NO")
      (libsource (lib "eagle-import") (part "SOLDERJUMPERNO"))
    )
    (comp (ref "SJ5")
      (value "SOLDERJUMPERNO")
      (footprint "eagle-import:SJ_2S-NO")
      (libsource (lib "eagle-import") (part "SOLDERJUMPERNO"))
    )
    (comp (ref "SJ6")
      (value "SOLDERJUMPERNO")
      (footprint "eagle-import:SJ_2S-NO")
      (libsource (lib "eagle-import") (part "SOLDERJUMPERNO"))
    )
    (comp (ref "SJ7")
      (value "SOLDERJUMPERNO")
      (footprint "eagle-import:SJ_2S-NO")
      (libsource (lib "eagle-import") (part "SOLDERJUMPERNO"))
    )
    (comp (ref "SJ8")
      (value "SOLDERJUMPERNO")
      (footprint "eagle-import:SJ_2S-NO")
      (libsource (lib "eagle-import") (part "SOLDERJUMPERNO"))
    )
    (comp (ref "SJ9")
      (value "SOLDERJUMPERNO")
      (footprint "eagle-import:SJ_2S-NO")
      (libsource (lib "eagle-import") (part "SOLDERJUMPERNO"))
    )
    (comp (ref "SJ10")
      (value "SOLDERJUMPERNO")
      (footprint "eagle-import:SJ_2S-NO")
      (libsource (lib "eagle-import") (part "SOLDERJUMPERNO"))
    )
    (comp (ref "SJ11")
      (value "SOLDERJUMPERNO")
      (footprint "eagle-import:SJ_2S-NO")
      (libsource (lib "eagle-import") (part "SOLDERJUMPERNO"))
    )
    (comp (ref "SJ12")
      (value "SOLDERJUMPERNO")
      (footprint "eagle-import:SJ_2S-NO")
      (libsource (lib "eagle-import") (part "SOLDERJUMPERNO"))
    )
    (comp (ref "SJ13")
      (value "SOLDERJUMPERNO")
      (footprint "eagle-import:SJ_2S-NO")
      (libsource (lib "eagle-import") (part "SOLDERJUMPERNO"))
    )
    (comp (ref "SJ14")
      (value "SOLDERJUMPERNO")
      (footprint "eagle-import:SJ_2S-NO")
      (libsource (lib "eagle-import") (part "SOLDERJUMPERNO"))
    )
    (comp (ref "SJ15")
      (value "SOLDERJUMPERNO")
      (footprint "eagle-import:SJ_2S-NO")
      (libsource (lib "eagle-import") (part "SOLDERJUMPERNO"))
    )
    (comp (ref "SJ16")
      (value "SOLDERJUMPERNO")
      (footprint "eagle-import:SJ_2S-NO")
      (libsource (lib "eagle-import") (part "SOLDERJUMPERNO"))
    )
    (comp (ref "SJ17")
      (value "SOLDERJUMPERNO")
      (footprint "eagle-import:SJ_2S-NO")
      (libsource (lib "eagle-import") (part "SOLDERJUMPERNO"))
    )
    (comp (ref "SJ18")
      (value "SOLDERJUMPERNO")
      (footprint "eagle-import:SJ_2S-NO")
      (libsource (lib "eagle-import") (part "SOLDERJUMPERNO"))
    )
    (comp (ref "SJ19")
      (value "SOLDERJUMPERNO")
      (footprint "eagle-import:SJ_2S-NO")
      (libsource (lib "eagle-import") (part "SOLDERJUMPERNO"))
    )
    (comp (ref "SJ20")
      (value "SOLDERJUMPERNO")
      (footprint "eagle-import:SJ_2S-NO")
      (libsource (lib "eagle-import") (part "SOLDERJUMPERNO"))
    )
    (comp (ref "SJ21")
      (value "SOLDERJUMPERNO")
      (footprint "eagle-import:SJ_2S-NO")
      (libsource (lib "eagle-import") (part "SOLDERJUMPERNO"))
    )
    (comp (ref "SJ22")
      (value "SJ-CONCON")
      (footprint "eagle-import:SJ-CON")
      (libsource (lib "eagle-import") (part "SJ-CONCON"))
    )
    (comp (ref "STM32F303VB")
      (value "STM32F303XB")
      (footprint "eagle-import:TQFP100")
      (libsource (lib "eagle-import") (part "STM32F303XB"))
    )
    (comp (ref "TP4")
      (value "TPB1,27")
      (footprint "eagle-import:B1,27")
      (libsource (lib "eagle-import") (part "TPB1,27"))
    )
    (comp (ref "TP5")
      (value "TPB1,27")
      (footprint "eagle-import:B1,27")
      (libsource (lib "eagle-import") (part "TPB1,27"))
    )
    (comp (ref "TP6")
      (value "TPB1,27")
      (footprint "eagle-import:B1,27")
      (libsource (lib "eagle-import") (part "TPB1,27"))
    )
    (comp (ref "U$2")
      (value "BOOST_MODULE")
      (footprint "eagle-import:BOOST")
      (libsource (lib "eagle-import") (part "BOOST_MODULE"))
    )
    (comp (ref "U1")
      (value "ESP32-WROOM-32D")
      (footprint "eagle-import:MODULE_ESP32-WROOM-32D")
      (fields (field (name "MF") "Espressif Systems"))
      (libsource (lib "eagle-import") (part "ESP32-WROOM-32D"))
    )
    (comp (ref "UART1")
      (value "M02PTH")
      (footprint "eagle-import:1X02")
      (libsource (lib "eagle-import") (part "M02PTH"))
    )
    (comp (ref "USB-C")
      (value "CSP-USC16-TR")
      (footprint "eagle-import:USB-C")
      (libsource (lib "eagle-import") (part "CSP-USC16-TR"))
    )
    (comp (ref "VREF_3V3")
      (value "MCP1501T-33E")
      (footprint "eagle-import:SOT95P280X145-6N")
      (libsource (lib "eagle-import") (part "MCP1501T-33E"))
    )
    (comp (ref "VT1")
      (value "2.1MMJACKSMT")
      (footprint "eagle-import:DCJACK_2MM_SMT")
      (libsource (lib "eagle-import") (part "2.1MMJACKSMT"))
    )
    (comp (ref "VT2")
      (value "2.1MMJACKSMT")
      (footprint "eagle-import:DCJACK_2MM_SMT")
      (libsource (lib "eagle-import") (part "2.1MMJACKSMT"))
    )
    (comp (ref "VT3")
      (value "2.1MMJACKSMT")
      (footprint "eagle-import:DCJACK_2MM_SMT")
      (libsource (lib "eagle-import") (part "2.1MMJACKSMT"))
    )
  )
  (nets
    (net (code "1") (name "+3V3") (class "Default")
      (node (ref "3POLE_1") (pin "P$1") (pinfunction "1_P$1") (pintype "bidirectional"))
      (node (ref "3POLE_2") (pin "P$1") (pinfunction "1_P$1") (pintype "bidirectional"))
      (node (ref "3POLE_3") (pin "P$1") (pinfunction "1_P$1") (pintype "bidirectional"))
      (node (ref "3POLE_6") (pin "P$1") (pinfunction "1_P$1") (pintype "bidirectional"))
      (node (ref "BOOT_STM") (pin "2") (pinfunction "2_2") (pintype "passive"))
      (node (ref "C13") (pin "1") (pinfunction "1_1") (pintype "passive"))
      (node (ref "C14") (pin "1") (pinfunction "1_1") (pintype "passive"))
      (node (ref "C17") (pin "1") (pinfunction "1_1") (pintype "passive"))
      (node (ref "C2") (pin "1") (pinfunction "1_1") (pintype "passive"))
      (node (ref "C24") (pin "1") (pinfunction "1_1") (pintype "passive"))
      (node (ref "C25") (pin "1") (pinfunction "1_1") (pintype "passive"))
      (node (ref "C26") (pin "1") (pinfunction "1_1") (pintype "passive"))
      (node (ref "C4") (pin "2") (pinfunction "2_2") (pintype "passive"))
      (node (ref "C40") (pin "1") (pinfunction "1_1") (pintype "passive"))
      (node (ref "C45") (pin "1") (pinfunction "1_1") (pintype "passive"))
      (node (ref "C5") (pin "2") (pinfunction "2_2") (pintype "passive"))
      (node (ref "C6") (pin "2") (pinfunction "2_2") (pintype "passive"))
      (node (ref "C8") (pin "2") (pinfunction "2_2") (pintype "passive"))
      (node (ref "C9") (pin "2") (pinfunction "2_2") (pintype "passive"))
      (node (ref "D22") (pin "K") (pinfunction "C_K") (pintype "passive"))
      (node (ref "D23") (pin "K") (pinfunction "C_K") (pintype "passive"))
      (node (ref "EXPANSION") (pin "24") (pinfunction "24_24") (pintype "passive"))
      (node (ref "EXPANSION") (pin "4") (pinfunction "4_4") (pintype "passive"))
      (node (ref "JP1") (pin "2") (pinfunction "2_2") (pintype "passive"))
      (node (ref "MCP1825") (pin "3") (pinfunction "+3V3_3") (pintype "power_in"))
      (node (ref "Q4") (pin "3") (pinfunction "D_3") (pintype "passive"))
      (node (ref "R1") (pin "2") (pinfunction "2_2") (pintype "passive"))
      (node (ref "R10") (pin "2") (pinfunction "2_2") (pintype "passive"))
      (node (ref "R22") (pin "2") (pinfunction "2_2") (pintype "passive"))
      (node (ref "RFM69HCW") (pin "9") (pinfunction "VDD_9") (pintype "power_in"))
      (node (ref "RJ45_1") (pin "2") (pinfunction "2_2") (pintype "bidirectional"))
      (node (ref "RJ45_2") (pin "2") (pinfunction "2_2") (pintype "bidirectional"))
      (node (ref "SJ1") (pin "2") (pinfunction "2_2") (pintype "passive"))
      (node (ref "SJ2") (pin "1") (pinfunction "1_1") (pintype "passive"))
      (node (ref "SJ22") (pin "1") (pinfunction "1_1") (pintype "passive"))
      (node (ref "STM32F303VB") (pin "100") (pinfunction "VDD_100") (pintype "bidirectional"))
      (node (ref "STM32F303VB") (pin "22") (pinfunction "VDDA_22") (pintype "bidirectional"))
      (node (ref "STM32F303VB") (pin "28") (pinfunction "VDD_28") (pintype "bidirectional"))
      (node (ref "STM32F303VB") (pin "50") (pinfunction "VDD_50") (pintype "bidirectional"))
      (node (ref "STM32F303VB") (pin "75") (pinfunction "VDD_75") (pintype "bidirectional"))
      (node (ref "U1") (pin "2") (pinfunction "3V3_2") (pintype "power_in"))
      (node (ref "VREF_3V3") (pin "4") (pinfunction "SHT_DN_4") (pintype "bidirectional"))
    )
    (net (code "2") (name "+5V") (class "Default")
      (node (ref "C18") (pin "1") (pinfunction "1_1") (pintype "passive"))
      (node (ref "C27") (pin "1") (pinfunction "1_1") (pintype "passive"))
      (node (ref "C28") (pin "1") (pinfunction "1_1") (pintype "passive"))
      (node (ref "C3") (pin "2") (pinfunction "2_2") (pintype "passive"))
      (node (ref "C42") (pin "1") (pinfunction "1_1") (pintype "passive"))
      (node (ref "C47") (pin "1") (pinfunction "1_1") (pintype "passive"))
      (node (ref "D20") (pin "C") (pinfunction "C_C") (pintype "passive"))
      (node (ref "D24") (pin "K") (pinfunction "C_K") (pintype "passive"))
      (node (ref "D40*") (pin "K") (pinfunction "C_K") (pintype "passive"))
      (node (ref "EXPANSION") (pin "2") (pinfunction "2_2") (pintype "passive"))
      (node (ref "JP1") (pin "3") (pinfunction "3_3") (pintype "passive"))
      (node (ref "JP3") (pin "3") (pinfunction "3_3") (pintype "passive"))
      (node (ref "MCP1825") (pin "1") (pinfunction "IN_1") (pintype "power_in"))
      (node (ref "PCB2") (pin "P$42") (pinfunction "5V_P$42") (pintype "bidirectional"))
      (node (ref "PCB2") (pin "P$44") (pinfunction "5V_P$44") (pintype "bidirectional"))
      (node (ref "RJ45_1") (pin "7") (pinfunction "7_7") (pintype "bidirectional"))
      (node (ref "RJ45_2") (pin "7") (pinfunction "7_7") (pintype "bidirectional"))
      (node (ref "TP4") (pin "TP") (pinfunction "TP_TP") (pintype "input"))
      (node (ref "U$2") (pin "IN+") (pinfunction "+5V_IN+") (pintype "bidirectional"))
      (node (ref "USB-C") (pin "A4/B9") (pinfunction "VBUS1_A4/B9") (pintype "passive"))
      (node (ref "USB-C") (pin "B4/A9") (pinfunction "VBUS2_B4/A9") (pintype "passive"))
      (node (ref "VREF_3V3") (pin "6") (pinfunction "VDD_6") (pintype "bidirectional"))
    )
    (net (code "3") (name "/+3V3_ADC") (class "Default")
      (node (ref "C11") (pin "1") (pinfunction "1_1") (pintype "passive"))
      (node (ref "C12") (pin "1") (pinfunction "1_1") (pintype "passive"))
      (node (ref "C7") (pin "1") (pinfunction "1_1") (pintype "passive"))
      (node (ref "SJ2") (pin "2") (pinfunction "2_2") (pintype "passive"))
      (node (ref "STM32F303VB") (pin "21") (pinfunction "VREF+_21") (pintype "bidirectional"))
      (node (ref "VREF_3V3") (pin "1") (pinfunction "OUT_1") (pintype "bidirectional"))
    )
    (net (code "4") (name "/24V") (class "Default")
      (node (ref "3POLE_7") (pin "P$3") (pinfunction "3_P$3") (pintype "bidirectional"))
      (node (ref "R11") (pin "2") (pinfunction "2_2") (pintype "passive"))
      (node (ref "R17") (pin "2") (pinfunction "2_2") (pintype "passive"))
      (node (ref "R9") (pin "2") (pinfunction "2_2") (pintype "passive"))
      (node (ref "U$2") (pin "OUT+") (pinfunction "24V_OUT+") (pintype "bidirectional"))
    )
    (net (code "5") (name "/ADC_2_RJ45IN") (class "Default")
      (node (ref "RJ45_2") (pin "8") (pinfunction "8_8") (pintype "bidirectional"))
    )
    (net (code "6") (name "/ADC_RJ45IN") (class "Default")
      (node (ref "RJ45_1") (pin "8") (pinfunction "8_8") (pintype "bidirectional"))
      (node (ref "STM32F303VB") (pin "54") (pinfunction "PB15_54") (pintype "bidirectional"))
    )
    (net (code "7") (name "/BIAS") (class "Default")
      (node (ref "CT1") (pin "P$1") (pinfunction "1_P$1") (pintype "bidirectional"))
      (node (ref "CT1") (pin "P$4") (pinfunction "4_P$4") (pintype "bidirectional"))
      (node (ref "CT2") (pin "P$1") (pinfunction "1_P$1") (pintype "bidirectional"))
      (node (ref "CT2") (pin "P$4") (pinfunction "4_P$4") (pintype "bidirectional"))
      (node (ref "CT3") (pin "P$1") (pinfunction "1_P$1") (pintype "bidirectional"))
      (node (ref "CT3") (pin "P$4") (pinfunction "4_P$4") (pintype "bidirectional"))
      (node (ref "CT4") (pin "P$1") (pinfunction "1_P$1") (pintype "bidirectional"))
      (node (ref "CT4") (pin "P$4") (pinfunction "4_P$4") (pintype "bidirectional"))
      (node (ref "CT5") (pin "P$1") (pinfunction "1_P$1") (pintype "bidirectional"))
      (node (ref "CT5") (pin "P$4") (pinfunction "4_P$4") (pintype "bidirectional"))
      (node (ref "CT6") (pin "P$1") (pinfunction "1_P$1") (pintype "bidirectional"))
      (node (ref "CT6") (pin "P$4") (pinfunction "4_P$4") (pintype "bidirectional"))
      (node (ref "CT7") (pin "P$1") (pinfunction "1_P$1") (pintype "bidirectional"))
      (node (ref "CT7") (pin "P$4") (pinfunction "4_P$4") (pintype "bidirectional"))
      (node (ref "CT8") (pin "P$1") (pinfunction "1_P$1") (pintype "bidirectional"))
      (node (ref "CT8") (pin "P$4") (pinfunction "4_P$4") (pintype "bidirectional"))
      (node (ref "CT9") (pin "P$1") (pinfunction "1_P$1") (pintype "bidirectional"))
      (node (ref "CT9") (pin "P$4") (pinfunction "4_P$4") (pintype "bidirectional"))
      (node (ref "D1") (pin "K") (pinfunction "C_K") (pintype "passive"))
      (node (ref "RB1") (pin "2") (pinfunction "2_2") (pintype "passive"))
      (node (ref "RB10") (pin "2") (pinfunction "2_2") (pintype "passive"))
      (node (ref "RB11") (pin "2") (pinfunction "2_2") (pintype "passive"))
      (node (ref "RB12") (pin "2") (pinfunction "2_2") (pintype "passive"))
      (node (ref "RB13") (pin "2") (pinfunction "2_2") (pintype "passive"))
      (node (ref "RB14") (pin "2") (pinfunction "2_2") (pintype "passive"))
      (node (ref "RB15") (pin "2") (pinfunction "2_2") (pintype "passive"))
      (node (ref "RB2") (pin "2") (pinfunction "2_2") (pintype "passive"))
      (node (ref "RB3") (pin "2") (pinfunction "2_2") (pintype "passive"))
      (node (ref "RB4") (pin "2") (pinfunction "2_2") (pintype "passive"))
      (node (ref "RB5") (pin "2") (pinfunction "2_2") (pintype "passive"))
      (node (ref "RB6") (pin "2") (pinfunction "2_2") (pintype "passive"))
      (node (ref "RVPU11") (pin "2") (pinfunction "2_2") (pintype "passive"))
      (node (ref "RVPU22") (pin "2") (pinfunction "2_2") (pintype "passive"))
      (node (ref "RVPU33") (pin "2") (pinfunction "2_2") (pintype "passive"))
      (node (ref "S11") (pin "2") (pinfunction "2_2") (pintype "passive"))
      (node (ref "S22") (pin "2") (pinfunction "2_2") (pintype "passive"))
      (node (ref "S33") (pin "2") (pinfunction "2_2") (pintype "passive"))
      (node (ref "STM32F303VB") (pin "51") (pinfunction "PB12_51") (pintype "bidirectional"))
      (node (ref "VT1") (pin "GND") (pinfunction "RING_GND") (pintype "bidirectional"))
      (node (ref "VT1") (pin "GNDBREAK") (pinfunction "RING_SW_GNDBREAK") (pintype "bidirectional"))
      (node (ref "VT2") (pin "GND") (pinfunction "RING_GND") (pintype "bidirectional"))
      (node (ref "VT2") (pin "GNDBREAK") (pinfunction "RING_SW_GNDBREAK") (pintype "bidirectional"))
      (node (ref "VT3") (pin "GND") (pinfunction "RING_GND") (pintype "bidirectional"))
      (node (ref "VT3") (pin "GNDBREAK") (pinfunction "RING_SW_GNDBREAK") (pintype "bidirectional"))
    )
    (net (code "8") (name "/BIAS_IN") (class "Default")
      (node (ref "C50*") (pin "2") (pinfunction "2_2") (pintype "passive"))
      (node (ref "R22") (pin "1") (pinfunction "1_1") (pintype "passive"))
      (node (ref "R23") (pin "2") (pinfunction "2_2") (pintype "passive"))
      (node (ref "STM32F303VB") (pin "58") (pinfunction "PD11_58") (pintype "bidirectional"))
    )
    (net (code "9") (name "/BOOT0") (class "Default")
      (node (ref "BOOT_STM") (pin "1") (pinfunction "1_1") (pintype "passive"))
      (node (ref "R2") (pin "1") (pinfunction "1_1") (pintype "passive"))
      (node (ref "STM32F303VB") (pin "94") (pinfunction "BOOT0_94") (pintype "bidirectional"))
    )
    (net (code "10") (name "/BUTTON1") (class "Default")
      (node (ref "PCB2") (pin "P$47") (pinfunction "GPIO4_P$47") (pintype "bidirectional"))
      (node (ref "S1") (pin "2") (pinfunction "2_2") (pintype "bidirectional"))
      (node (ref "STM32F303VB") (pin "53") (pinfunction "PB14_53") (pintype "bidirectional"))
    )
    (net (code "12") (name "/CSESP_STM32") (class "Default")
      (node (ref "SJ19") (pin "1") (pinfunction "1_1") (pintype "passive"))
      (node (ref "U1") (pin "27") (pinfunction "IO16_27") (pintype "bidirectional"))
    )
    (net (code "13") (name "/CS_RFM69") (class "Default")
      (node (ref "PCB2") (pin "P$64") (pinfunction "GPIO8_P$64") (pintype "bidirectional"))
      (node (ref "RFM69HCW") (pin "14") (pinfunction "~{SEL}_14") (pintype "input"))
      (node (ref "SJ13") (pin "2") (pinfunction "2_2") (pintype "passive"))
    )
    (net (code "14") (name "/CS_STM32") (class "Default")
      (node (ref "SJ14") (pin "1") (pinfunction "1_1") (pintype "passive"))
      (node (ref "SJ19") (pin "2") (pinfunction "2_2") (pintype "passive"))
      (node (ref "SJ8") (pin "2") (pinfunction "2_2") (pintype "passive"))
    )
    (net (code "15") (name "/CT1") (class "Default")
      (node (ref "CF1") (pin "2") (pinfunction "2_2") (pintype "passive"))
      (node (ref "RF1") (pin "2") (pinfunction "2_2") (pintype "passive"))
      (node (ref "STM32F303VB") (pin "44") (pinfunction "PE13_44") (pintype "bidirectional"))
    )
    (net (code "16") (name "/CT1_EX") (class "Default")
      (node (ref "EXPANSION") (pin "3") (pinfunction "3_3") (pintype "passive"))
      (node (ref "STM32F303VB") (pin "29") (pinfunction "PA4_29") (pintype "bidirectional"))
    )
    (net (code "17") (name "/CT2") (class "Default")
      (node (ref "CF2") (pin "2") (pinfunction "2_2") (pintype "passive"))
      (node (ref "RF2") (pin "2") (pinfunction "2_2") (pintype "passive"))
      (node (ref "STM32F303VB") (pin "43") (pinfunction "PE12_43") (pintype "bidirectional"))
    )
    (net (code "18") (name "/CT2_EX") (class "Default")
      (node (ref "EXPANSION") (pin "6") (pinfunction "6_6") (pintype "passive"))
      (node (ref "STM32F303VB") (pin "30") (pinfunction "PA5_30") (pintype "bidirectional"))
    )
    (net (code "19") (name "/CT3") (class "Default")
      (node (ref "CF3") (pin "2") (pinfunction "2_2") (pintype "passive"))
      (node (ref "RF3") (pin "2") (pinfunction "2_2") (pintype "passive"))
      (node (ref "STM32F303VB") (pin "42") (pinfunction "PE11_42") (pintype "bidirectional"))
    )
    (net (code "20") (name "/CT3_EX") (class "Default")
      (node (ref "EXPANSION") (pin "5") (pinfunction "5_5") (pintype "passive"))
      (node (ref "STM32F303VB") (pin "31") (pinfunction "PA6_31") (pintype "bidirectional"))
    )
    (net (code "21") (name "/CT4") (class "Default")
      (node (ref "CF4") (pin "2") (pinfunction "2_2") (pintype "passive"))
      (node (ref "RF4") (pin "2") (pinfunction "2_2") (pintype "passive"))
      (node (ref "STM32F303VB") (pin "41") (pinfunction "PE10_41") (pintype "bidirectional"))
    )
    (net (code "22") (name "/CT4_EX") (class "Default")
      (node (ref "EXPANSION") (pin "8") (pinfunction "8_8") (pintype "passive"))
      (node (ref "STM32F303VB") (pin "32") (pinfunction "PA7_32") (pintype "bidirectional"))
    )
    (net (code "23") (name "/CT5") (class "Default")
      (node (ref "CF5") (pin "2") (pinfunction "2_2") (pintype "passive"))
      (node (ref "RF5") (pin "2") (pinfunction "2_2") (pintype "passive"))
      (node (ref "STM32F303VB") (pin "40") (pinfunction "PE9_40") (pintype "bidirectional"))
    )
    (net (code "24") (name "/CT5_EX") (class "Default")
      (node (ref "EXPANSION") (pin "7") (pinfunction "7_7") (pintype "passive"))
      (node (ref "STM32F303VB") (pin "33") (pinfunction "PC4_33") (pintype "bidirectional"))
    )
    (net (code "25") (name "/CT6") (class "Default")
      (node (ref "CF6") (pin "2") (pinfunction "2_2") (pintype "passive"))
      (node (ref "RF6") (pin "2") (pinfunction "2_2") (pintype "passive"))
      (node (ref "STM32F303VB") (pin "39") (pinfunction "PE8_39") (pintype "bidirectional"))
    )
    (net (code "26") (name "/CT6_EX") (class "Default")
      (node (ref "EXPANSION") (pin "10") (pinfunction "10_10") (pintype "passive"))
      (node (ref "STM32F303VB") (pin "15") (pinfunction "PC0_15") (pintype "bidirectional"))
    )
    (net (code "27") (name "/CT7") (class "Default")
      (node (ref "CF7") (pin "2") (pinfunction "2_2") (pintype "passive"))
      (node (ref "RF7") (pin "2") (pinfunction "2_2") (pintype "passive"))
      (node (ref "STM32F303VB") (pin "38") (pinfunction "PE7_38") (pintype "bidirectional"))
    )
    (net (code "28") (name "/CT7_EX") (class "Default")
      (node (ref "EXPANSION") (pin "9") (pinfunction "9_9") (pintype "passive"))
      (node (ref "STM32F303VB") (pin "16") (pinfunction "PC1_16") (pintype "bidirectional"))
    )
    (net (code "29") (name "/CT8") (class "Default")
      (node (ref "CF8") (pin "2") (pinfunction "2_2") (pintype "passive"))
      (node (ref "RF8") (pin "2") (pinfunction "2_2") (pintype "passive"))
      (node (ref "STM32F303VB") (pin "36") (pinfunction "PB1_36") (pintype "bidirectional"))
    )
    (net (code "30") (name "/CT9") (class "Default")
      (node (ref "CF9") (pin "2") (pinfunction "2_2") (pintype "passive"))
      (node (ref "RF9") (pin "2") (pinfunction "2_2") (pintype "passive"))
      (node (ref "STM32F303VB") (pin "35") (pinfunction "PB0_35") (pintype "bidirectional"))
    )
    (net (code "31") (name "/D+") (class "Default")
      (node (ref "R6") (pin "2") (pinfunction "2_2") (pintype "passive"))
      (node (ref "STM32F303VB") (pin "71") (pinfunction "PA12_71") (pintype "bidirectional"))
      (node (ref "TP5") (pin "TP") (pinfunction "TP_TP") (pintype "input"))
      (node (ref "USB-C") (pin "A6") (pinfunction "D1+_A6") (pintype "passive"))
    )
    (net (code "32") (name "/D-") (class "Default")
      (node (ref "STM32F303VB") (pin "70") (pinfunction "PA11_70") (pintype "bidirectional"))
      (node (ref "TP6") (pin "TP") (pinfunction "TP_TP") (pintype "input"))
      (node (ref "USB-C") (pin "A7") (pinfunction "D1-_A7") (pintype "passive"))
    )
    (net (code "33") (name "/DIO0") (class "Default")
      (node (ref "PCB2") (pin "P$58") (pinfunction "GPIO24_P$58") (pintype "bidirectional"))
      (node (ref "RFM69HCW") (pin "2") (pinfunction "~{IRQ}_2") (pintype "output"))
      (node (ref "STM32F303VB") (pin "89") (pinfunction "PB3_89") (pintype "bidirectional"))
      (node (ref "U1") (pin "24") (pinfunction "IO2_24") (pintype "bidirectional"))
    )
    (net (code "34") (name "/DS18B20_2_RJ45") (class "Default")
      (node (ref "RJ45_2") (pin "4") (pinfunction "4_4") (pintype "bidirectional"))
    )
    (net (code "35") (name "/DS18B20_RJ45") (class "Default")
      (node (ref "R1") (pin "1") (pinfunction "1_1") (pintype "passive"))
      (node (ref "RJ45_1") (pin "4") (pinfunction "4_4") (pintype "bidirectional"))
      (node (ref "STM32F303VB") (pin "66") (pinfunction "PC9_66") (pintype "bidirectional"))
    )
    (net (code "36") (name "/HSE_IN") (class "Default")
      (node (ref "HSE") (pin "1") (pinfunction "1_1") (pintype "passive"))
      (node (ref "STM32F303VB") (pin "12") (pinfunction "PF0/OSC_IN_12") (pintype "bidirectional"))
    )
    (net (code "37") (name "/HSE_OUT") (class "Default")
      (node (ref "HSE") (pin "3") (pinfunction "2_3") (pintype "passive"))
      (node (ref "STM32F303VB") (pin "13") (pinfunction "PF1/OSC_OUT_13") (pintype "bidirectional"))
    )
    (net (code "38") (name "/HSPICS0") (class "Default")
      (node (ref "SJ13") (pin "1") (pinfunction "1_1") (pintype "passive"))
      (node (ref "U1") (pin "23") (pinfunction "IO15_23") (pintype "bidirectional"))
    )
    (net (code "39") (name "/HSPID") (class "Default")
      (node (ref "SJ9") (pin "1") (pinfunction "1_1") (pintype "passive"))
      (node (ref "U1") (pin "16") (pinfunction "IO13_16") (pintype "bidirectional"))
    )
    (net (code "40") (name "/HSPIQ") (class "Default")
      (node (ref "SJ4") (pin "1") (pinfunction "1_1") (pintype "passive"))
      (node (ref "U1") (pin "14") (pinfunction "IO12_14") (pintype "bidirectional"))
    )
    (net (code "41") (name "/HSPI_CLK") (class "Default")
      (node (ref "SJ10") (pin "1") (pinfunction "1_1") (pintype "passive"))
      (node (ref "U1") (pin "13") (pinfunction "IO14_13") (pintype "bidirectional"))
    )
    (net (code "42") (name "/IO1_EX") (class "Default")
      (node (ref "EXPANSION") (pin "15") (pinfunction "15_15") (pintype "passive"))
      (node (ref "STM32F303VB") (pin "97") (pinfunction "PE0_97") (pintype "bidirectional"))
    )
    (net (code "43") (name "/IO2_EX") (class "Default")
      (node (ref "EXPANSION") (pin "16") (pinfunction "16_16") (pintype "passive"))
      (node (ref "STM32F303VB") (pin "98") (pinfunction "PE1_98") (pintype "bidirectional"))
    )
    (net (code "44") (name "/IO3_EX") (class "Default")
      (node (ref "EXPANSION") (pin "17") (pinfunction "17_17") (pintype "passive"))
      (node (ref "STM32F303VB") (pin "1") (pinfunction "PE2_1") (pintype "bidirectional"))
    )
    (net (code "45") (name "/IO4_EX") (class "Default")
      (node (ref "EXPANSION") (pin "18") (pinfunction "18_18") (pintype "passive"))
      (node (ref "STM32F303VB") (pin "2") (pinfunction "PE3_2") (pintype "bidirectional"))
    )
    (net (code "46") (name "/IO5_EX") (class "Default")
      (node (ref "EXPANSION") (pin "19") (pinfunction "19_19") (pintype "passive"))
      (node (ref "STM32F303VB") (pin "3") (pinfunction "PE4_3") (pintype "bidirectional"))
    )
    (net (code "47") (name "/IO6_EX") (class "Default")
      (node (ref "EXPANSION") (pin "21") (pinfunction "21_21") (pintype "passive"))
      (node (ref "STM32F303VB") (pin "4") (pinfunction "PE5_4") (pintype "bidirectional"))
    )
    (net (code "48") (name "/IO7_EX") (class "Default")
      (node (ref "EXPANSION") (pin "23") (pinfunction "23_23") (pintype "passive"))
      (node (ref "STM32F303VB") (pin "5") (pinfunction "PE6_5") (pintype "bidirectional"))
    )
    (net (code "49") (name "/IO8_EX") (class "Default")
      (node (ref "EXPANSION") (pin "25") (pinfunction "25_25") (pintype "passive"))
      (node (ref "STM32F303VB") (pin "91") (pinfunction "PB5_91") (pintype "bidirectional"))
    )
    (net (code "50") (name "/IO11_EX") (class "Default")
      (node (ref "STM32F303VB") (pin "95") (pinfunction "PB8_95") (pintype "bidirectional"))
    )
    (net (code "51") (name "/LED1_GREEN") (class "Default")
      (node (ref "R3") (pin "2") (pinfunction "2_2") (pintype "passive"))
      (node (ref "STM32F303VB") (pin "55") (pinfunction "PD8_55") (pintype "bidirectional"))
    )
    (net (code "52") (name "/LED2_YELLOW") (class "Default")
      (node (ref "R4") (pin "2") (pinfunction "2_2") (pintype "passive"))
      (node (ref "STM32F303VB") (pin "56") (pinfunction "PD9_56") (pintype "bidirectional"))
    )
    (net (code "53") (name "/LED3_RED") (class "Default")
      (node (ref "R5") (pin "2") (pinfunction "2_2") (pintype "passive"))
      (node (ref "STM32F303VB") (pin "57") (pinfunction "PD10_57") (pintype "bidirectional"))
    )
    (net (code "54") (name "/MBUS_INPUT") (class "Default")
      (node (ref "3POLE_7") (pin "P$2") (pinfunction "2_P$2") (pintype "bidirectional"))
      (node (ref "Q1") (pin "2") (pinfunction "E_2") (pintype "passive"))
      (node (ref "R17") (pin "1") (pinfunction "1_1") (pintype "passive"))
    )
    (net (code "55") (name "/MBUS_RX") (class "Default")
      (node (ref "PCB2") (pin "P$56") (pinfunction "GPIO23_P$56") (pintype "bidirectional"))
      (node (ref "R18") (pin "2") (pinfunction "2_2") (pintype "passive"))
      (node (ref "SJ11") (pin "2") (pinfunction "2_2") (pintype "passive"))
    )
    (net (code "56") (name "/MBUS_TX") (class "Default")
      (node (ref "PCB2") (pin "P$52") (pinfunction "GPIO18_P$52") (pintype "bidirectional"))
      (node (ref "R19") (pin "2") (pinfunction "2_2") (pintype "passive"))
      (node (ref "SJ12") (pin "2") (pinfunction "2_2") (pintype "passive"))
    )
    (net (code "57") (name "/MISO") (class "Default")
      (node (ref "RFM69HCW") (pin "1") (pinfunction "SDO_1") (pintype "output"))
      (node (ref "SJ16") (pin "2") (pinfunction "2_2") (pintype "passive"))
      (node (ref "SJ4") (pin "2") (pinfunction "2_2") (pintype "passive"))
      (node (ref "SJ6") (pin "1") (pinfunction "1_1") (pintype "passive"))
    )
    (net (code "58") (name "/MOSI") (class "Default")
      (node (ref "RFM69HCW") (pin "12") (pinfunction "SDI_12") (pintype "input"))
      (node (ref "SJ17") (pin "2") (pinfunction "2_2") (pintype "passive"))
      (node (ref "SJ5") (pin "1") (pinfunction "1_1") (pintype "passive"))
      (node (ref "SJ9") (pin "2") (pinfunction "2_2") (pintype "passive"))
    )
    (net (code "59") (name "/N$21") (class "Default")
      (node (ref "R6") (pin "1") (pinfunction "1_1") (pintype "passive"))
      (node (ref "SJ22") (pin "2") (pinfunction "2_2") (pintype "passive"))
    )
    (net (code "60") (name "/NRST_STM") (class "Default")
      (node (ref "JP3") (pin "6") (pinfunction "6_6") (pintype "passive"))
      (node (ref "PCB2") (pin "P$71") (pinfunction "GPIO6_P$71") (pintype "bidirectional"))
      (node (ref "S2") (pin "2") (pinfunction "2_2") (pintype "bidirectional"))
      (node (ref "STM32F303VB") (pin "14") (pinfunction "NRST_14") (pintype "bidirectional"))
      (node (ref "U1") (pin "30") (pinfunction "IO18_30") (pintype "bidirectional"))
    )
    (net (code "61") (name "/PC14") (class "Default")
      (node (ref "LSE") (pin "P$1") (pinfunction "1_P$1") (pintype "passive"))
      (node (ref "STM32F303VB") (pin "8") (pinfunction "PC14/OSC32_IN_8") (pintype "bidirectional"))
    )
    (net (code "62") (name "/PC15") (class "Default")
      (node (ref "LSE") (pin "P$4") (pinfunction "2_P$4") (pintype "passive"))
      (node (ref "STM32F303VB") (pin "9") (pinfunction "PC15/OSC32_OUT_9") (pintype "bidirectional"))
    )
    (net (code "63") (name "/PULSE1_RJ45") (class "Default")
      (node (ref "C41") (pin "1") (pinfunction "1_1") (pintype "passive"))
      (node (ref "RJ45_1") (pin "6") (pinfunction "6_6") (pintype "bidirectional"))
      (node (ref "STM32F303VB") (pin "67") (pinfunction "PA8_67") (pintype "bidirectional"))
    )
    (net (code "64") (name "/PULSE_2_RJ45") (class "Default")
      (node (ref "C46") (pin "1") (pinfunction "1_1") (pintype "passive"))
      (node (ref "RJ45_2") (pin "6") (pinfunction "6_6") (pintype "bidirectional"))
    )
    (net (code "65") (name "/PUSHIN_1") (class "Default")
      (node (ref "3POLE_1") (pin "P$2") (pinfunction "2_P$2") (pintype "bidirectional"))
      (node (ref "D14") (pin "K") (pinfunction "C_K") (pintype "passive"))
      (node (ref "STM32F303VB") (pin "63") (pinfunction "PC6_63") (pintype "bidirectional"))
    )
    (net (code "66") (name "/PUSHIN_2") (class "Default")
      (node (ref "3POLE_2") (pin "P$2") (pinfunction "2_P$2") (pintype "bidirectional"))
      (node (ref "C10") (pin "1") (pinfunction "1_1") (pintype "passive"))
      (node (ref "D15") (pin "K") (pinfunction "C_K") (pintype "passive"))
      (node (ref "STM32F303VB") (pin "64") (pinfunction "PC7_64") (pintype "bidirectional"))
    )
    (net (code "67") (name "/PUSHIN_3") (class "Default")
      (node (ref "3POLE_3") (pin "P$2") (pinfunction "2_P$2") (pintype "bidirectional"))
      (node (ref "C15") (pin "1") (pinfunction "1_1") (pintype "passive"))
      (node (ref "D16") (pin "K") (pinfunction "C_K") (pintype "passive"))
      (node (ref "STM32F303VB") (pin "65") (pinfunction "PC8_65") (pintype "bidirectional"))
    )
    (net (code "68") (name "/PUSHIN_BYANT") (class "Default")
      (node (ref "3POLE_6") (pin "P$2") (pinfunction "2_P$2") (pintype "bidirectional"))
      (node (ref "C21") (pin "1") (pinfunction "1_1") (pintype "passive"))
      (node (ref "D19") (pin "K") (pinfunction "C_K") (pintype "passive"))
      (node (ref "STM32F303VB") (pin "96") (pinfunction "PB9_96") (pintype "bidirectional"))
    )
    (net (code "69") (name "/RPI_GPIO16") (class "Default")
      (node (ref "PCB2") (pin "P$76") (pinfunction "GPIO16_P$76") (pintype "bidirectional"))
      (node (ref "STM32F303VB") (pin "59") (pinfunction "PD12_59") (pintype "bidirectional"))
    )
    (net (code "70") (name "/RPI_GPIO20") (class "Default")
      (node (ref "PCB2") (pin "P$78") (pinfunction "GPIO20_P$78") (pintype "bidirectional"))
      (node (ref "STM32F303VB") (pin "60") (pinfunction "PD13_60") (pintype "bidirectional"))
    )
    (net (code "71") (name "/RPI_MISO") (class "Default")
      (node (ref "PCB2") (pin "P$61") (pinfunction "GPIO9_P$61") (pintype "bidirectional"))
      (node (ref "SJ6") (pin "2") (pinfunction "2_2") (pintype "passive"))
    )
    (net (code "72") (name "/RPI_MOSI") (class "Default")
      (node (ref "PCB2") (pin "P$59") (pinfunction "GPIO10_P$59") (pintype "bidirectional"))
      (node (ref "SJ5") (pin "2") (pinfunction "2_2") (pintype "passive"))
    )
    (net (code "73") (name "/RPI_SPI_CLK") (class "Default")
      (node (ref "PCB2") (pin "P$63") (pinfunction "GPIO11_P$63") (pintype "bidirectional"))
      (node (ref "SJ7") (pin "2") (pinfunction "2_2") (pintype "passive"))
    )
    (net (code "74") (name "/RST_RFM") (class "Default")
      (node (ref "PCB2") (pin "P$69") (pinfunction "GPIO5_P$69") (pintype "bidirectional"))
      (node (ref "RFM69HCW") (pin "6") (pinfunction "~{RES}_6") (pintype "bidirectional"))
      (node (ref "U1") (pin "28") (pinfunction "IO17_28") (pintype "bidirectional"))
    )
    (net (code "75") (name "/SCL") (class "Default")
      (node (ref "EXPANSION") (pin "22") (pinfunction "22_22") (pintype "passive"))
      (node (ref "PCB2") (pin "P$68") (pinfunction "ID_SC*_P$68") (pintype "bidirectional"))
      (node (ref "STM32F303VB") (pin "92") (pinfunction "PB6_92") (pintype "bidirectional"))
      (node (ref "U1") (pin "36") (pinfunction "IO22_36") (pintype "bidirectional"))
    )
    (net (code "76") (name "/SDA") (class "Default")
      (node (ref "EXPANSION") (pin "20") (pinfunction "20_20") (pintype "passive"))
      (node (ref "PCB2") (pin "P$67") (pinfunction "ID_SD*_P$67") (pintype "bidirectional"))
      (node (ref "STM32F303VB") (pin "93") (pinfunction "PB7_93") (pintype "bidirectional"))
      (node (ref "U1") (pin "33") (pinfunction "IO21_33") (pintype "bidirectional"))
    )
    (net (code "77") (name "/SPI3_CLK") (class "Default")
      (node (ref "SJ15") (pin "1") (pinfunction "1_1") (pintype "passive"))
      (node (ref "STM32F303VB") (pin "78") (pinfunction "PC10_78") (pintype "bidirectional"))
    )
    (net (code "78") (name "/SPI3_CS") (class "Default")
      (node (ref "SJ14") (pin "2") (pinfunction "2_2") (pintype "passive"))
      (node (ref "STM32F303VB") (pin "77") (pinfunction "PA15_77") (pintype "bidirectional"))
    )
    (net (code "79") (name "/SPI3_CS_ESP") (class "Default")
      (node (ref "STM32F303VB") (pin "84") (pinfunction "PD3_84") (pintype "bidirectional"))
    )
    (net (code "80") (name "/SPI3_MISO") (class "Default")
      (node (ref "SJ16") (pin "1") (pinfunction "1_1") (pintype "passive"))
      (node (ref "STM32F303VB") (pin "79") (pinfunction "PC11_79") (pintype "bidirectional"))
    )
    (net (code "81") (name "/SPI3_MOSI") (class "Default")
      (node (ref "SJ17") (pin "1") (pinfunction "1_1") (pintype "passive"))
      (node (ref "STM32F303VB") (pin "80") (pinfunction "PC12_80") (pintype "bidirectional"))
    )
    (net (code "82") (name "/SPI_CLK") (class "Default")
      (node (ref "RFM69HCW") (pin "13") (pinfunction "SCK_13") (pintype "input"))
      (node (ref "SJ10") (pin "2") (pinfunction "2_2") (pintype "passive"))
      (node (ref "SJ15") (pin "2") (pinfunction "2_2") (pintype "passive"))
      (node (ref "SJ7") (pin "1") (pinfunction "1_1") (pintype "passive"))
    )
    (net (code "83") (name "/SWCLK") (class "Default")
      (node (ref "JP3") (pin "7") (pinfunction "7_7") (pintype "passive"))
      (node (ref "STM32F303VB") (pin "76") (pinfunction "PA14_76") (pintype "bidirectional"))
    )
    (net (code "84") (name "/SWDIO") (class "Default")
      (node (ref "JP3") (pin "8") (pinfunction "8_8") (pintype "passive"))
      (node (ref "STM32F303VB") (pin "72") (pinfunction "PA13_72") (pintype "bidirectional"))
    )
    (net (code "85") (name "/UART1_RX") (class "Default")
      (node (ref "PCB2") (pin "P$48") (pinfunction "GPIO14_P$48") (pintype "bidirectional"))
      (node (ref "SJ11") (pin "1") (pinfunction "1_1") (pintype "passive"))
      (node (ref "SJ20") (pin "1") (pinfunction "1_1") (pintype "passive"))
    )
    (net (code "86") (name "/UART1_TX") (class "Default")
      (node (ref "PCB2") (pin "P$50") (pinfunction "GPIO15_P$50") (pintype "bidirectional"))
      (node (ref "SJ12") (pin "1") (pinfunction "1_1") (pintype "passive"))
      (node (ref "SJ21") (pin "1") (pinfunction "1_1") (pintype "passive"))
    )
    (net (code "87") (name "/UART2_RX") (class "Default")
      (node (ref "JP3") (pin "4") (pinfunction "4_4") (pintype "passive"))
      (node (ref "STM32F303VB") (pin "26") (pinfunction "PA3_26") (pintype "bidirectional"))
    )
    (net (code "88") (name "/UART2_TX") (class "Default")
      (node (ref "JP3") (pin "5") (pinfunction "5_5") (pintype "passive"))
      (node (ref "STM32F303VB") (pin "25") (pinfunction "PA2_25") (pintype "bidirectional"))
      (node (ref "STM32F303VB") (pin "86") (pinfunction "PD5_86") (pintype "bidirectional"))
    )
    (net (code "89") (name "/USART3_RX") (class "Default")
      (node (ref "SJ3") (pin "2") (pinfunction "2_2") (pintype "passive"))
      (node (ref "STM32F303VB") (pin "48") (pinfunction "PB11_48") (pintype "bidirectional"))
    )
    (net (code "90") (name "/USART3_TX") (class "Default")
      (node (ref "SJ18") (pin "2") (pinfunction "2_2") (pintype "passive"))
      (node (ref "STM32F303VB") (pin "47") (pinfunction "PB10_47") (pintype "bidirectional"))
    )
    (net (code "91") (name "/VBAT") (class "Default")
      (node (ref "C23") (pin "+") (pinfunction "+_+") (pintype "passive"))
      (node (ref "Q4") (pin "2") (pinfunction "S_2") (pintype "passive"))
      (node (ref "STM32F303VB") (pin "6") (pinfunction "VBAT_6") (pintype "bidirectional"))
    )
    (net (code "92") (name "/VSIG1") (class "Default")
      (node (ref "CFV1") (pin "2") (pinfunction "2_2") (pintype "passive"))
      (node (ref "D2") (pin "K") (pinfunction "C_K") (pintype "passive"))
      (node (ref "RFV1") (pin "2") (pinfunction "2_2") (pintype "passive"))
      (node (ref "STM32F303VB") (pin "23") (pinfunction "PA0_23") (pintype "bidirectional"))
    )
    (net (code "93") (name "/VSIG2") (class "Default")
      (node (ref "CFV2") (pin "2") (pinfunction "2_2") (pintype "passive"))
      (node (ref "D3") (pin "K") (pinfunction "C_K") (pintype "passive"))
      (node (ref "RFV2") (pin "2") (pinfunction "2_2") (pintype "passive"))
      (node (ref "STM32F303VB") (pin "24") (pinfunction "PA1_24") (pintype "bidirectional"))
    )
    (net (code "94") (name "/VSIG3") (class "Default")
      (node (ref "CFV3") (pin "2") (pinfunction "2_2") (pintype "passive"))
      (node (ref "D4") (pin "K") (pinfunction "C_K") (pintype "passive"))
      (node (ref "RFV3") (pin "2") (pinfunction "2_2") (pintype "passive"))
      (node (ref "STM32F303VB") (pin "27") (pinfunction "PF4_27") (pintype "bidirectional"))
    )
    (net (code "95") (name "/VSIG4") (class "Default")
      (node (ref "STM32F303VB") (pin "17") (pinfunction "PC2_17") (pintype "bidirectional"))
    )
    (net (code "96") (name "/VSIG5") (class "Default")
      (node (ref "STM32F303VB") (pin "18") (pinfunction "PC3_18") (pintype "bidirectional"))
    )
    (net (code "97") (name "/VSIG6") (class "Default")
      (node (ref "STM32F303VB") (pin "19") (pinfunction "PF2_19") (pintype "bidirectional"))
    )
    (net (code "98") (name "/VT1_EX") (class "Default")
      (node (ref "EXPANSION") (pin "11") (pinfunction "11_11") (pintype "passive"))
    )
    (net (code "99") (name "/VT2_EX") (class "Default")
      (node (ref "EXPANSION") (pin "12") (pinfunction "12_12") (pintype "passive"))
    )
    (net (code "100") (name "/VT3_EX") (class "Default")
      (node (ref "EXPANSION") (pin "13") (pinfunction "13_13") (pintype "passive"))
    )
    (net (code "101") (name "GND") (class "Default")
      (node (ref "3POLE_1") (pin "P$3") (pinfunction "3_P$3") (pintype "bidirectional"))
      (node (ref "3POLE_2") (pin "P$3") (pinfunction "3_P$3") (pintype "bidirectional"))
      (node (ref "3POLE_3") (pin "P$3") (pinfunction "3_P$3") (pintype "bidirectional"))
      (node (ref "3POLE_6") (pin "P$3") (pinfunction "3_P$3") (pintype "bidirectional"))
      (node (ref "3POLE_7") (pin "P$1") (pinfunction "1_P$1") (pintype "bidirectional"))
      (node (ref "BOOT_ESP") (pin "1") (pinfunction "1_1") (pintype "passive"))
      (node (ref "C10") (pin "2") (pinfunction "2_2") (pintype "passive"))
      (node (ref "C11") (pin "2") (pinfunction "2_2") (pintype "passive"))
      (node (ref "C12") (pin "2") (pinfunction "2_2") (pintype "passive"))
      (node (ref "C13") (pin "2") (pinfunction "2_2") (pintype "passive"))
      (node (ref "C14") (pin "2") (pinfunction "2_2") (pintype "passive"))
      (node (ref "C15") (pin "2") (pinfunction "2_2") (pintype "passive"))
      (node (ref "C17") (pin "2") (pinfunction "2_2") (pintype "passive"))
      (node (ref "C18") (pin "2") (pinfunction "2_2") (pintype "passive"))
      (node (ref "C2") (pin "2") (pinfunction "2_2") (pintype "passive"))
      (node (ref "C21") (pin "2") (pinfunction "2_2") (pintype "passive"))
      (node (ref "C23") (pin "-") (pinfunction "-_-") (pintype "passive"))
      (node (ref "C24") (pin "2") (pinfunction "2_2") (pintype "passive"))
      (node (ref "C25") (pin "2") (pinfunction "2_2") (pintype "passive"))
      (node (ref "C26") (pin "2") (pinfunction "2_2") (pintype "passive"))
      (node (ref "C27") (pin "2") (pinfunction "2_2") (pintype "passive"))
      (node (ref "C28") (pin "2") (pinfunction "2_2") (pintype "passive"))
      (node (ref "C3") (pin "1") (pinfunction "1_1") (pintype "passive"))
      (node (ref "C4") (pin "1") (pinfunction "1_1") (pintype "passive"))
      (node (ref "C40") (pin "2") (pinfunction "2_2") (pintype "passive"))
      (node (ref "C41") (pin "2") (pinfunction "2_2") (pintype "passive"))
      (node (ref "C42") (pin "2") (pinfunction "2_2") (pintype "passive"))
      (node (ref "C45") (pin "2") (pinfunction "2_2") (pintype "passive"))
      (node (ref "C46") (pin "2") (pinfunction "2_2") (pintype "passive"))
      (node (ref "C47") (pin "2") (pinfunction "2_2") (pintype "passive"))
      (node (ref "C5") (pin "1") (pinfunction "1_1") (pintype "passive"))
      (node (ref "C50*") (pin "1") (pinfunction "1_1") (pintype "passive"))
      (node (ref "C6") (pin "1") (pinfunction "1_1") (pintype "passive"))
      (node (ref "C7") (pin "2") (pinfunction "2_2") (pintype "passive"))
      (node (ref "C8") (pin "1") (pinfunction "1_1") (pintype "passive"))
      (node (ref "C9") (pin "1") (pinfunction "1_1") (pintype "passive"))
      (node (ref "CF1") (pin "1") (pinfunction "1_1") (pintype "passive"))
      (node (ref "CF2") (pin "1") (pinfunction "1_1") (pintype "passive"))
      (node (ref "CF3") (pin "1") (pinfunction "1_1") (pintype "passive"))
      (node (ref "CF4") (pin "1") (pinfunction "1_1") (pintype "passive"))
      (node (ref "CF5") (pin "1") (pinfunction "1_1") (pintype "passive"))
      (node (ref "CF6") (pin "1") (pinfunction "1_1") (pintype "passive"))
      (node (ref "CF7") (pin "1") (pinfunction "1_1") (pintype "passive"))
      (node (ref "CF8") (pin "1") (pinfunction "1_1") (pintype "passive"))
      (node (ref "CF9") (pin "1") (pinfunction "1_1") (pintype "passive"))
      (node (ref "CFV1") (pin "1") (pinfunction "1_1") (pintype "passive"))
      (node (ref "CFV2") (pin "1") (pinfunction "1_1") (pintype "passive"))
      (node (ref "CFV3") (pin "1") (pinfunction "1_1") (pintype "passive"))
      (node (ref "D1") (pin "A") (pinfunction "A_A") (pintype "passive"))
      (node (ref "D10") (pin "A") (pinfunction "A_A") (pintype "passive"))
      (node (ref "D11") (pin "A") (pinfunction "A_A") (pintype "passive"))
      (node (ref "D12") (pin "A") (pinfunction "A_A") (pintype "passive"))
      (node (ref "D13") (pin "A") (pinfunction "A_A") (pintype "passive"))
      (node (ref "D14") (pin "A") (pinfunction "A_A") (pintype "passive"))
      (node (ref "D15") (pin "A") (pinfunction "A_A") (pintype "passive"))
      (node (ref "D16") (pin "A") (pinfunction "A_A") (pintype "passive"))
      (node (ref "D19") (pin "A") (pinfunction "A_A") (pintype "passive"))
      (node (ref "D2") (pin "A") (pinfunction "A_A") (pintype "passive"))
      (node (ref "D20") (pin "A") (pinfunction "A_A") (pintype "passive"))
      (node (ref "D22") (pin "A") (pinfunction "A_A") (pintype "passive"))
      (node (ref "D23") (pin "A") (pinfunction "A_A") (pintype "passive"))
      (node (ref "D25") (pin "A") (pinfunction "A_A") (pintype "passive"))
      (node (ref "D3") (pin "A") (pinfunction "A_A") (pintype "passive"))
      (node (ref "D4") (pin "A") (pinfunction "A_A") (pintype "passive"))
      (node (ref "D41*") (pin "A") (pinfunction "A_A") (pintype "passive"))
      (node (ref "D5") (pin "A") (pinfunction "A_A") (pintype "passive"))
      (node (ref "D6") (pin "A") (pinfunction "A_A") (pintype "passive"))
      (node (ref "D7") (pin "A") (pinfunction "A_A") (pintype "passive"))
      (node (ref "D8") (pin "A") (pinfunction "A_A") (pintype "passive"))
      (node (ref "D9") (pin "A") (pinfunction "A_A") (pintype "passive"))
      (node (ref "EXPANSION") (pin "1") (pinfunction "1_1") (pintype "passive"))
      (node (ref "EXPANSION") (pin "14") (pinfunction "14_14") (pintype "passive"))
      (node (ref "EXPANSION") (pin "26") (pinfunction "26_26") (pintype "passive"))
      (node (ref "J$1") (pin "GND@0") (pinfunction "GND_GND@0") (pintype "bidirectional"))
      (node (ref "J$1") (pin "GND@1") (pinfunction "GND_GND@1") (pintype "bidirectional"))
      (node (ref "J$1") (pin "GND@2") (pinfunction "GND_GND@2") (pintype "bidirectional"))
      (node (ref "J$1") (pin "GND@3") (pinfunction "GND_GND@3") (pintype "bidirectional"))
      (node (ref "JP1") (pin "1") (pinfunction "1_1") (pintype "passive"))
      (node (ref "JP3") (pin "1") (pinfunction "1_1") (pintype "passive"))
      (node (ref "LED1") (pin "C") (pinfunction "C_C") (pintype "passive"))
      (node (ref "LED2") (pin "C") (pinfunction "C_C") (pintype "passive"))
      (node (ref "LED3") (pin "C") (pinfunction "C_C") (pintype "passive"))
      (node (ref "LED4") (pin "C") (pinfunction "C_C") (pintype "passive"))
      (node (ref "MCP1825") (pin "2") (pinfunction "GND_2") (pintype "power_in"))
      (node (ref "MCP1825") (pin "4") (pinfunction "GND_4") (pintype "power_in"))
      (node (ref "PCB2") (pin "P$46") (pinfunction "GND_P$46") (pintype "bidirectional"))
      (node (ref "PCB2") (pin "P$49") (pinfunction "GND_P$49") (pintype "bidirectional"))
      (node (ref "PCB2") (pin "P$54") (pinfunction "GND_P$54") (pintype "bidirectional"))
      (node (ref "PCB2") (pin "P$60") (pinfunction "GND_P$60") (pintype "bidirectional"))
      (node (ref "PCB2") (pin "P$65") (pinfunction "GND_P$65") (pintype "bidirectional"))
      (node (ref "PCB2") (pin "P$70") (pinfunction "GND_P$70") (pintype "bidirectional"))
      (node (ref "PCB2") (pin "P$74") (pinfunction "GND_P$74") (pintype "bidirectional"))
      (node (ref "PCB2") (pin "P$79") (pinfunction "GND_P$79") (pintype "bidirectional"))
      (node (ref "Q2") (pin "2") (pinfunction "E_2") (pintype "passive"))
      (node (ref "Q3") (pin "2") (pinfunction "E_2") (pintype "passive"))
      (node (ref "Q4") (pin "1") (pinfunction "G_1") (pintype "passive"))
      (node (ref "R14") (pin "1") (pinfunction "1_1") (pintype "passive"))
      (node (ref "R15") (pin "1") (pinfunction "1_1") (pintype "passive"))
      (node (ref "R16") (pin "1") (pinfunction "1_1") (pintype "passive"))
      (node (ref "R2") (pin "2") (pinfunction "2_2") (pintype "passive"))
      (node (ref "R23") (pin "1") (pinfunction "1_1") (pintype "passive"))
      (node (ref "RFM69HCW") (pin "10") (pinfunction "GND_10") (pintype "passive"))
      (node (ref "RFM69HCW") (pin "7") (pinfunction "GND_7") (pintype "passive"))
      (node (ref "RJ45_1") (pin "1") (pinfunction "1_1") (pintype "bidirectional"))
      (node (ref "RJ45_1") (pin "3") (pinfunction "3_3") (pintype "bidirectional"))
      (node (ref "RJ45_1") (pin "5") (pinfunction "5_5") (pintype "bidirectional"))
      (node (ref "RJ45_2") (pin "1") (pinfunction "1_1") (pintype "bidirectional"))
      (node (ref "RJ45_2") (pin "3") (pinfunction "3_3") (pintype "bidirectional"))
      (node (ref "RJ45_2") (pin "5") (pinfunction "5_5") (pintype "bidirectional"))
      (node (ref "S1") (pin "1") (pinfunction "1_1") (pintype "bidirectional"))
      (node (ref "S2") (pin "1") (pinfunction "1_1") (pintype "bidirectional"))
      (node (ref "STM32F303VB") (pin "20") (pinfunction "VSSA/VREF-_20") (pintype "bidirectional"))
      (node (ref "STM32F303VB") (pin "49") (pinfunction "VSS_49") (pintype "bidirectional"))
      (node (ref "STM32F303VB") (pin "74") (pinfunction "VSS_74") (pintype "bidirectional"))
      (node (ref "STM32F303VB") (pin "99") (pinfunction "VSS_99") (pintype "bidirectional"))
      (node (ref "U$2") (pin "P$1") (pinfunction "GND_P$1") (pintype "bidirectional"))
      (node (ref "U$2") (pin "P$2") (pinfunction "GND._P$2") (pintype "bidirectional"))
      (node (ref "U1") (pin "1") (pinfunction "GND_1") (pintype "power_in"))
      (node (ref "U1") (pin "15") (pinfunction "GND_15") (pintype "power_in"))
      (node (ref "U1") (pin "31") (pinfunction "IO19_31") (pintype "bidirectional"))
      (node (ref "U1") (pin "38") (pinfunction "GND_38") (pintype "power_in"))
      (node (ref "U1") (pin "39") (pinfunction "GND_39") (pintype "power_in"))
      (node (ref "USB-C") (pin "A1/B12") (pinfunction "GND1_A1/B12") (pintype "passive"))
      (node (ref "USB-C") (pin "B1/A12") (pinfunction "GND2_B1/A12") (pintype "passive"))
      (node (ref "USB-C") (pin "GND1") (pinfunction "SHIELD_GND1") (pintype "bidirectional"))
      (node (ref "USB-C") (pin "GND2") (pinfunction "SHIELD_GND2") (pintype "bidirectional"))
      (node (ref "USB-C") (pin "GND3") (pinfunction "SHIELD_GND3") (pintype "bidirectional"))
      (node (ref "USB-C") (pin "GND4") (pinfunction "SHIELD_GND4") (pintype "bidirectional"))
      (node (ref "VREF_3V3") (pin "2") (pinfunction "GND_2") (pintype "bidirectional"))
      (node (ref "VREF_3V3") (pin "3") (pinfunction "GND_3") (pintype "bidirectional"))
      (node (ref "VREF_3V3") (pin "5") (pinfunction "GND_5") (pintype "bidirectional"))
    )
    (net (code "102") (name "Net-(C16-Pad1)") (class "Default")
      (node (ref "C16") (pin "1") (pinfunction "1_1") (pintype "passive"))
      (node (ref "JP1") (pin "6") (pinfunction "6_6") (pintype "passive"))
    )
    (net (code "103") (name "Net-(CT1-2)") (class "Default")
      (node (ref "CT1") (pin "P$2") (pinfunction "2_P$2") (pintype "bidirectional"))
      (node (ref "D13") (pin "K") (pinfunction "C_K") (pintype "passive"))
      (node (ref "RB18") (pin "1") (pinfunction "1_1") (pintype "passive"))
      (node (ref "RB9") (pin "1") (pinfunction "1_1") (pintype "passive"))
      (node (ref "RF9") (pin "1") (pinfunction "1_1") (pintype "passive"))
    )
    (net (code "104") (name "Net-(CT2-2)") (class "Default")
      (node (ref "CT2") (pin "P$2") (pinfunction "2_P$2") (pintype "bidirectional"))
      (node (ref "D12") (pin "K") (pinfunction "C_K") (pintype "passive"))
      (node (ref "RB17") (pin "1") (pinfunction "1_1") (pintype "passive"))
      (node (ref "RB8") (pin "1") (pinfunction "1_1") (pintype "passive"))
      (node (ref "RF8") (pin "1") (pinfunction "1_1") (pintype "passive"))
    )
    (net (code "105") (name "Net-(CT3-2)") (class "Default")
      (node (ref "CT3") (pin "P$2") (pinfunction "2_P$2") (pintype "bidirectional"))
      (node (ref "D11") (pin "K") (pinfunction "C_K") (pintype "passive"))
      (node (ref "RB16") (pin "1") (pinfunction "1_1") (pintype "passive"))
      (node (ref "RB7") (pin "1") (pinfunction "1_1") (pintype "passive"))
      (node (ref "RF7") (pin "1") (pinfunction "1_1") (pintype "passive"))
    )
    (net (code "106") (name "Net-(CT4-2)") (class "Default")
      (node (ref "CT4") (pin "P$2") (pinfunction "2_P$2") (pintype "bidirectional"))
      (node (ref "D10") (pin "K") (pinfunction "C_K") (pintype "passive"))
      (node (ref "RB13") (pin "1") (pinfunction "1_1") (pintype "passive"))
      (node (ref "RB6") (pin "1") (pinfunction "1_1") (pintype "passive"))
      (node (ref "RF6") (pin "1") (pinfunction "1_1") (pintype "passive"))
    )
    (net (code "107") (name "Net-(CT5-2)") (class "Default")
      (node (ref "CT5") (pin "P$2") (pinfunction "2_P$2") (pintype "bidirectional"))
      (node (ref "D9") (pin "K") (pinfunction "C_K") (pintype "passive"))
      (node (ref "RB14") (pin "1") (pinfunction "1_1") (pintype "passive"))
      (node (ref "RB5") (pin "1") (pinfunction "1_1") (pintype "passive"))
      (node (ref "RF5") (pin "1") (pinfunction "1_1") (pintype "passive"))
    )
    (net (code "108") (name "Net-(CT6-2)") (class "Default")
      (node (ref "CT6") (pin "P$2") (pinfunction "2_P$2") (pintype "bidirectional"))
      (node (ref "D8") (pin "K") (pinfunction "C_K") (pintype "passive"))
      (node (ref "RB15") (pin "1") (pinfunction "1_1") (pintype "passive"))
      (node (ref "RB4") (pin "1") (pinfunction "1_1") (pintype "passive"))
      (node (ref "RF4") (pin "1") (pinfunction "1_1") (pintype "passive"))
    )
    (net (code "109") (name "Net-(CT7-2)") (class "Default")
      (node (ref "CT7") (pin "P$2") (pinfunction "2_P$2") (pintype "bidirectional"))
      (node (ref "D7") (pin "K") (pinfunction "C_K") (pintype "passive"))
      (node (ref "RB12") (pin "1") (pinfunction "1_1") (pintype "passive"))
      (node (ref "RB3") (pin "1") (pinfunction "1_1") (pintype "passive"))
      (node (ref "RF3") (pin "1") (pinfunction "1_1") (pintype "passive"))
    )
    (net (code "110") (name "Net-(CT8-2)") (class "Default")
      (node (ref "CT8") (pin "P$2") (pinfunction "2_P$2") (pintype "bidirectional"))
      (node (ref "D6") (pin "K") (pinfunction "C_K") (pintype "passive"))
      (node (ref "RB11") (pin "1") (pinfunction "1_1") (pintype "passive"))
      (node (ref "RB2") (pin "1") (pinfunction "1_1") (pintype "passive"))
      (node (ref "RF2") (pin "1") (pinfunction "1_1") (pintype "passive"))
    )
    (net (code "111") (name "Net-(CT9-2)") (class "Default")
      (node (ref "CT9") (pin "P$2") (pinfunction "2_P$2") (pintype "bidirectional"))
      (node (ref "D5") (pin "K") (pinfunction "C_K") (pintype "passive"))
      (node (ref "RB1") (pin "1") (pinfunction "1_1") (pintype "passive"))
      (node (ref "RB10") (pin "1") (pinfunction "1_1") (pintype "passive"))
      (node (ref "RF1") (pin "1") (pinfunction "1_1") (pintype "passive"))
    )
    (net (code "112") (name "Net-(D25-C)") (class "Default")
      (node (ref "D24") (pin "A") (pinfunction "A_A") (pintype "passive"))
      (node (ref "D25") (pin "K") (pinfunction "C_K") (pintype "passive"))
    )
    (net (code "113") (name "Net-(D41*-C)") (class "Default")
      (node (ref "D40*") (pin "A") (pinfunction "A_A") (pintype "passive"))
      (node (ref "D41*") (pin "K") (pinfunction "C_K") (pintype "passive"))
    )
    (net (code "114") (name "Net-(J$1-SIGNAL)") (class "Default")
      (node (ref "J$1") (pin "SIG") (pinfunction "SIGNAL_SIG") (pintype "bidirectional"))
      (node (ref "RFM69HCW") (pin "8") (pinfunction "ANT_8") (pintype "bidirectional"))
    )
    (net (code "115") (name "Net-(JP3-Pad2)") (class "Default")
      (node (ref "JP3") (pin "2") (pinfunction "2_2") (pintype "passive"))
      (node (ref "SJ1") (pin "1") (pinfunction "1_1") (pintype "passive"))
    )
    (net (code "116") (name "Net-(LED1-PadA)") (class "Default")
      (node (ref "LED1") (pin "A") (pinfunction "A_A") (pintype "passive"))
      (node (ref "R3") (pin "1") (pinfunction "1_1") (pintype "passive"))
    )
    (net (code "117") (name "Net-(LED2-PadA)") (class "Default")
      (node (ref "LED2") (pin "A") (pinfunction "A_A") (pintype "passive"))
      (node (ref "R4") (pin "1") (pinfunction "1_1") (pintype "passive"))
    )
    (net (code "118") (name "Net-(LED3-PadA)") (class "Default")
      (node (ref "LED3") (pin "A") (pinfunction "A_A") (pintype "passive"))
      (node (ref "R5") (pin "1") (pinfunction "1_1") (pintype "passive"))
    )
    (net (code "119") (name "Net-(LED4-PadA)") (class "Default")
      (node (ref "LED4") (pin "A") (pinfunction "A_A") (pintype "passive"))
      (node (ref "R10") (pin "1") (pinfunction "1_1") (pintype "passive"))
    )
    (net (code "120") (name "Net-(PCB2-GPIO12)") (class "Default")
      (node (ref "PCB2") (pin "P$72") (pinfunction "GPIO12_P$72") (pintype "bidirectional"))
      (node (ref "SJ8") (pin "1") (pinfunction "1_1") (pintype "passive"))
    )
    (net (code "121") (name "Net-(Q1-B)") (class "Default")
      (node (ref "Q1") (pin "1") (pinfunction "B_1") (pintype "passive"))
      (node (ref "Q3") (pin "3") (pinfunction "C_3") (pintype "passive"))
      (node (ref "R14") (pin "2") (pinfunction "2_2") (pintype "passive"))
      (node (ref "R9") (pin "1") (pinfunction "1_1") (pintype "passive"))
    )
    (net (code "122") (name "Net-(Q1-C)") (class "Default")
      (node (ref "Q1") (pin "3") (pinfunction "C_3") (pintype "passive"))
      (node (ref "Q2") (pin "1") (pinfunction "B_1") (pintype "passive"))
      (node (ref "R16") (pin "2") (pinfunction "2_2") (pintype "passive"))
    )
    (net (code "123") (name "Net-(Q2-C)") (class "Default")
      (node (ref "Q2") (pin "3") (pinfunction "C_3") (pintype "passive"))
      (node (ref "R11") (pin "1") (pinfunction "1_1") (pintype "passive"))
      (node (ref "R15") (pin "2") (pinfunction "2_2") (pintype "passive"))
      (node (ref "R19") (pin "1") (pinfunction "1_1") (pintype "passive"))
    )
    (net (code "124") (name "Net-(Q3-B)") (class "Default")
      (node (ref "Q3") (pin "1") (pinfunction "B_1") (pintype "passive"))
      (node (ref "R18") (pin "1") (pinfunction "1_1") (pintype "passive"))
    )
    (net (code "125") (name "Net-(RB16-Pad2)") (class "Default")
      (node (ref "RB16") (pin "2") (pinfunction "2_2") (pintype "passive"))
      (node (ref "RB7") (pin "2") (pinfunction "2_2") (pintype "passive"))
      (node (ref "S33") (pin "1") (pinfunction "1_1") (pintype "passive"))
    )
    (net (code "126") (name "Net-(RB17-Pad2)") (class "Default")
      (node (ref "RB17") (pin "2") (pinfunction "2_2") (pintype "passive"))
      (node (ref "RB8") (pin "2") (pinfunction "2_2") (pintype "passive"))
      (node (ref "S22") (pin "1") (pinfunction "1_1") (pintype "passive"))
    )
    (net (code "127") (name "Net-(RB18-Pad2)") (class "Default")
      (node (ref "RB18") (pin "2") (pinfunction "2_2") (pintype "passive"))
      (node (ref "RB9") (pin "2") (pinfunction "2_2") (pintype "passive"))
      (node (ref "S11") (pin "1") (pinfunction "1_1") (pintype "passive"))
    )
    (net (code "128") (name "Net-(RFV1-Pad1)") (class "Default")
      (node (ref "RFV1") (pin "1") (pinfunction "1_1") (pintype "passive"))
      (node (ref "RVPU1") (pin "1") (pinfunction "1_1") (pintype "passive"))
      (node (ref "RVPU11") (pin "1") (pinfunction "1_1") (pintype "passive"))
    )
    (net (code "129") (name "Net-(RFV2-Pad1)") (class "Default")
      (node (ref "RFV2") (pin "1") (pinfunction "1_1") (pintype "passive"))
      (node (ref "RVPU2") (pin "1") (pinfunction "1_1") (pintype "passive"))
      (node (ref "RVPU22") (pin "1") (pinfunction "1_1") (pintype "passive"))
    )
    (net (code "130") (name "Net-(RFV3-Pad1)") (class "Default")
      (node (ref "RFV3") (pin "1") (pinfunction "1_1") (pintype "passive"))
      (node (ref "RVPU3") (pin "2") (pinfunction "2_2") (pintype "passive"))
      (node (ref "RVPU33") (pin "1") (pinfunction "1_1") (pintype "passive"))
    )
    (net (code "131") (name "Net-(STM32F303VB-PA9)") (class "Default")
      (node (ref "STM32F303VB") (pin "68") (pinfunction "PA9_68") (pintype "bidirectional"))
      (node (ref "UART1") (pin "2") (pinfunction "2_2") (pintype "passive"))
    )
    (net (code "132") (name "Net-(STM32F303VB-PA10)") (class "Default")
      (node (ref "STM32F303VB") (pin "69") (pinfunction "PA10_69") (pintype "bidirectional"))
      (node (ref "UART1") (pin "1") (pinfunction "1_1") (pintype "passive"))
    )
    (net (code "133") (name "Net-(U1-EN)") (class "Default")
      (node (ref "C16") (pin "2") (pinfunction "2_2") (pintype "passive"))
      (node (ref "U1") (pin "3") (pinfunction "EN_3") (pintype "input"))
    )
    (net (code "134") (name "Net-(U1-IO0)") (class "Default")
      (node (ref "BOOT_ESP") (pin "2") (pinfunction "2_2") (pintype "passive"))
      (node (ref "U1") (pin "25") (pinfunction "IO0_25") (pintype "bidirectional"))
    )
    (net (code "135") (name "Net-(U1-RXD0)") (class "Default")
      (node (ref "JP1") (pin "4") (pinfunction "4_4") (pintype "passive"))
      (node (ref "SJ18") (pin "1") (pinfunction "1_1") (pintype "passive"))
      (node (ref "SJ21") (pin "2") (pinfunction "2_2") (pintype "passive"))
      (node (ref "U1") (pin "34") (pinfunction "RXD0_34") (pintype "bidirectional"))
    )
    (net (code "136") (name "Net-(U1-TXD0)") (class "Default")
      (node (ref "JP1") (pin "5") (pinfunction "5_5") (pintype "passive"))
      (node (ref "SJ20") (pin "2") (pinfunction "2_2") (pintype "passive"))
      (node (ref "SJ3") (pin "1") (pinfunction "1_1") (pintype "passive"))
      (node (ref "U1") (pin "35") (pinfunction "TXD0_35") (pintype "bidirectional"))
    )
    (net (code "137") (name "Net-(VT1-TIP)") (class "Default")
      (node (ref "RVPU1") (pin "2") (pinfunction "2_2") (pintype "passive"))
      (node (ref "VT1") (pin "PWR2") (pinfunction "TIP_PWR2") (pintype "bidirectional"))
    )
    (net (code "138") (name "Net-(VT2-TIP)") (class "Default")
      (node (ref "RVPU2") (pin "2") (pinfunction "2_2") (pintype "passive"))
      (node (ref "VT2") (pin "PWR2") (pinfunction "TIP_PWR2") (pintype "bidirectional"))
    )
    (net (code "139") (name "Net-(VT3-TIP)") (class "Default")
      (node (ref "RVPU3") (pin "1") (pinfunction "1_1") (pintype "passive"))
      (node (ref "VT3") (pin "PWR2") (pinfunction "TIP_PWR2") (pintype "bidirectional"))
    )
    (net (code "140") (name "unconnected-(CT1-3-PadP$3)") (class "Default")
      (node (ref "CT1") (pin "P$3") (pinfunction "3_P$3") (pintype "bidirectional"))
    )
    (net (code "141") (name "unconnected-(CT2-3-PadP$3)") (class "Default")
      (node (ref "CT2") (pin "P$3") (pinfunction "3_P$3") (pintype "bidirectional"))
    )
    (net (code "142") (name "unconnected-(CT3-3-PadP$3)") (class "Default")
      (node (ref "CT3") (pin "P$3") (pinfunction "3_P$3") (pintype "bidirectional"))
    )
    (net (code "143") (name "unconnected-(CT4-3-PadP$3)") (class "Default")
      (node (ref "CT4") (pin "P$3") (pinfunction "3_P$3") (pintype "bidirectional"))
    )
    (net (code "144") (name "unconnected-(CT5-3-PadP$3)") (class "Default")
      (node (ref "CT5") (pin "P$3") (pinfunction "3_P$3") (pintype "bidirectional"))
    )
    (net (code "145") (name "unconnected-(CT6-3-PadP$3)") (class "Default")
      (node (ref "CT6") (pin "P$3") (pinfunction "3_P$3") (pintype "bidirectional"))
    )
    (net (code "146") (name "unconnected-(CT7-3-PadP$3)") (class "Default")
      (node (ref "CT7") (pin "P$3") (pinfunction "3_P$3") (pintype "bidirectional"))
    )
    (net (code "147") (name "unconnected-(CT8-3-PadP$3)") (class "Default")
      (node (ref "CT8") (pin "P$3") (pinfunction "3_P$3") (pintype "bidirectional"))
    )
    (net (code "148") (name "unconnected-(CT9-3-PadP$3)") (class "Default")
      (node (ref "CT9") (pin "P$3") (pinfunction "3_P$3") (pintype "bidirectional"))
    )
    (net (code "149") (name "unconnected-(PCB2-3V3-PadP$41)") (class "Default")
      (node (ref "PCB2") (pin "P$41") (pinfunction "3V3_P$41") (pintype "bidirectional"))
    )
    (net (code "150") (name "unconnected-(PCB2-3V3-PadP$57)") (class "Default")
      (node (ref "PCB2") (pin "P$57") (pinfunction "3V3_P$57") (pintype "bidirectional"))
    )
    (net (code "151") (name "unconnected-(PCB2-GPIO2-PadP$43)") (class "Default")
      (node (ref "PCB2") (pin "P$43") (pinfunction "GPIO2_P$43") (pintype "bidirectional"))
    )
    (net (code "152") (name "unconnected-(PCB2-GPIO3-PadP$45)") (class "Default")
      (node (ref "PCB2") (pin "P$45") (pinfunction "GPIO3_P$45") (pintype "bidirectional"))
    )
    (net (code "153") (name "unconnected-(PCB2-GPIO7-PadP$66)") (class "Default")
      (node (ref "PCB2") (pin "P$66") (pinfunction "GPIO7_P$66") (pintype "bidirectional"))
    )
    (net (code "154") (name "unconnected-(PCB2-GPIO13-PadP$73)") (class "Default")
      (node (ref "PCB2") (pin "P$73") (pinfunction "GPIO13_P$73") (pintype "bidirectional"))
    )
    (net (code "155") (name "unconnected-(PCB2-GPIO17-PadP$51)") (class "Default")
      (node (ref "PCB2") (pin "P$51") (pinfunction "GPIO17_P$51") (pintype "bidirectional"))
    )
    (net (code "156") (name "unconnected-(PCB2-GPIO19-PadP$75)") (class "Default")
      (node (ref "PCB2") (pin "P$75") (pinfunction "GPIO19_P$75") (pintype "bidirectional"))
    )
    (net (code "157") (name "unconnected-(PCB2-GPIO21-PadP$80)") (class "Default")
      (node (ref "PCB2") (pin "P$80") (pinfunction "GPIO21_P$80") (pintype "bidirectional"))
    )
    (net (code "158") (name "unconnected-(PCB2-GPIO22-PadP$55)") (class "Default")
      (node (ref "PCB2") (pin "P$55") (pinfunction "GPIO22_P$55") (pintype "bidirectional"))
    )
    (net (code "159") (name "unconnected-(PCB2-GPIO25-PadP$62)") (class "Default")
      (node (ref "PCB2") (pin "P$62") (pinfunction "GPIO25_P$62") (pintype "bidirectional"))
    )
    (net (code "160") (name "unconnected-(PCB2-GPIO26-PadP$77)") (class "Default")
      (node (ref "PCB2") (pin "P$77") (pinfunction "GPIO26_P$77") (pintype "bidirectional"))
    )
    (net (code "161") (name "unconnected-(PCB2-GPIO27-PadP$53)") (class "Default")
      (node (ref "PCB2") (pin "P$53") (pinfunction "GPIO27_P$53") (pintype "bidirectional"))
    )
    (net (code "162") (name "unconnected-(RFM69HCW-CLK-Pad5)") (class "Default")
      (node (ref "RFM69HCW") (pin "5") (pinfunction "CLK_5") (pintype "output"))
    )
    (net (code "163") (name "unconnected-(RFM69HCW-DCLK{slash}CFIL{slash}FFIT-Pad4)") (class "Default")
      (node (ref "RFM69HCW") (pin "4") (pinfunction "DCLK/CFIL/FFIT_4") (pintype "bidirectional"))
    )
    (net (code "164") (name "unconnected-(RFM69HCW-FSK{slash}DATA{slash}NFFS-Pad3)") (class "Default")
      (node (ref "RFM69HCW") (pin "3") (pinfunction "FSK/DATA/NFFS_3") (pintype "bidirectional"))
    )
    (net (code "165") (name "unconnected-(RFM69HCW-~{INT}-Pad11)") (class "Default")
      (node (ref "RFM69HCW") (pin "11") (pinfunction "~{INT}_11") (pintype "bidirectional"))
    )
    (net (code "166") (name "unconnected-(STM32F303VB-PB2-Pad37)") (class "Default")
      (node (ref "STM32F303VB") (pin "37") (pinfunction "PB2_37") (pintype "bidirectional"))
    )
    (net (code "167") (name "unconnected-(STM32F303VB-PB4-Pad90)") (class "Default")
      (node (ref "STM32F303VB") (pin "90") (pinfunction "PB4_90") (pintype "bidirectional"))
    )
    (net (code "168") (name "unconnected-(STM32F303VB-PB13-Pad52)") (class "Default")
      (node (ref "STM32F303VB") (pin "52") (pinfunction "PB13_52") (pintype "bidirectional"))
    )
    (net (code "169") (name "unconnected-(STM32F303VB-PC5-Pad34)") (class "Default")
      (node (ref "STM32F303VB") (pin "34") (pinfunction "PC5_34") (pintype "bidirectional"))
    )
    (net (code "170") (name "unconnected-(STM32F303VB-PC13-Pad7)") (class "Default")
      (node (ref "STM32F303VB") (pin "7") (pinfunction "PC13_7") (pintype "bidirectional"))
    )
    (net (code "171") (name "unconnected-(STM32F303VB-PD0-Pad81)") (class "Default")
      (node (ref "STM32F303VB") (pin "81") (pinfunction "PD0_81") (pintype "bidirectional"))
    )
    (net (code "172") (name "unconnected-(STM32F303VB-PD1-Pad82)") (class "Default")
      (node (ref "STM32F303VB") (pin "82") (pinfunction "PD1_82") (pintype "bidirectional"))
    )
    (net (code "173") (name "unconnected-(STM32F303VB-PD2-Pad83)") (class "Default")
      (node (ref "STM32F303VB") (pin "83") (pinfunction "PD2_83") (pintype "bidirectional"))
    )
    (net (code "174") (name "unconnected-(STM32F303VB-PD4-Pad85)") (class "Default")
      (node (ref "STM32F303VB") (pin "85") (pinfunction "PD4_85") (pintype "bidirectional"))
    )
    (net (code "175") (name "unconnected-(STM32F303VB-PD6-Pad87)") (class "Default")
      (node (ref "STM32F303VB") (pin "87") (pinfunction "PD6_87") (pintype "bidirectional"))
    )
    (net (code "176") (name "unconnected-(STM32F303VB-PD7-Pad88)") (class "Default")
      (node (ref "STM32F303VB") (pin "88") (pinfunction "PD7_88") (pintype "bidirectional"))
    )
    (net (code "177") (name "unconnected-(STM32F303VB-PD14-Pad61)") (class "Default")
      (node (ref "STM32F303VB") (pin "61") (pinfunction "PD14_61") (pintype "bidirectional"))
    )
    (net (code "178") (name "unconnected-(STM32F303VB-PD15-Pad62)") (class "Default")
      (node (ref "STM32F303VB") (pin "62") (pinfunction "PD15_62") (pintype "bidirectional"))
    )
    (net (code "179") (name "unconnected-(STM32F303VB-PE14-Pad45)") (class "Default")
      (node (ref "STM32F303VB") (pin "45") (pinfunction "PE14_45") (pintype "bidirectional"))
    )
    (net (code "180") (name "unconnected-(STM32F303VB-PE15-Pad46)") (class "Default")
      (node (ref "STM32F303VB") (pin "46") (pinfunction "PE15_46") (pintype "bidirectional"))
    )
    (net (code "181") (name "unconnected-(STM32F303VB-PF6-Pad73)") (class "Default")
      (node (ref "STM32F303VB") (pin "73") (pinfunction "PF6_73") (pintype "bidirectional"))
    )
    (net (code "182") (name "unconnected-(STM32F303VB-PF9-Pad10)") (class "Default")
      (node (ref "STM32F303VB") (pin "10") (pinfunction "PF9_10") (pintype "bidirectional"))
    )
    (net (code "183") (name "unconnected-(STM32F303VB-PF10-Pad11)") (class "Default")
      (node (ref "STM32F303VB") (pin "11") (pinfunction "PF10_11") (pintype "bidirectional"))
    )
    (net (code "184") (name "unconnected-(U1-IO4-Pad26)") (class "Default")
      (node (ref "U1") (pin "26") (pinfunction "IO4_26") (pintype "bidirectional"))
    )
    (net (code "185") (name "unconnected-(U1-IO5-Pad29)") (class "Default")
      (node (ref "U1") (pin "29") (pinfunction "IO5_29") (pintype "bidirectional"))
    )
    (net (code "186") (name "unconnected-(U1-IO23-Pad37)") (class "Default")
      (node (ref "U1") (pin "37") (pinfunction "IO23_37") (pintype "bidirectional"))
    )
    (net (code "187") (name "unconnected-(U1-IO25-Pad10)") (class "Default")
      (node (ref "U1") (pin "10") (pinfunction "IO25_10") (pintype "bidirectional"))
    )
    (net (code "188") (name "unconnected-(U1-IO26-Pad11)") (class "Default")
      (node (ref "U1") (pin "11") (pinfunction "IO26_11") (pintype "bidirectional"))
    )
    (net (code "189") (name "unconnected-(U1-IO27-Pad12)") (class "Default")
      (node (ref "U1") (pin "12") (pinfunction "IO27_12") (pintype "bidirectional"))
    )
    (net (code "190") (name "unconnected-(U1-IO32-Pad8)") (class "Default")
      (node (ref "U1") (pin "8") (pinfunction "IO32_8") (pintype "bidirectional"))
    )
    (net (code "191") (name "unconnected-(U1-IO33-Pad9)") (class "Default")
      (node (ref "U1") (pin "9") (pinfunction "IO33_9") (pintype "bidirectional"))
    )
    (net (code "192") (name "unconnected-(U1-IO34-Pad6)") (class "Default")
      (node (ref "U1") (pin "6") (pinfunction "IO34_6") (pintype "bidirectional"))
    )
    (net (code "193") (name "unconnected-(U1-IO35-Pad7)") (class "Default")
      (node (ref "U1") (pin "7") (pinfunction "IO35_7") (pintype "bidirectional"))
    )
    (net (code "194") (name "unconnected-(U1-SCL{slash}CLK-Pad20)") (class "Default")
      (node (ref "U1") (pin "20") (pinfunction "SCL/CLK_20") (pintype "bidirectional"))
    )
    (net (code "195") (name "unconnected-(U1-SCS{slash}CMD-Pad19)") (class "Default")
      (node (ref "U1") (pin "19") (pinfunction "SCS/CMD_19") (pintype "bidirectional"))
    )
    (net (code "196") (name "unconnected-(U1-SDI{slash}SD1-Pad22)") (class "Default")
      (node (ref "U1") (pin "22") (pinfunction "SDI/SD1_22") (pintype "bidirectional"))
    )
    (net (code "197") (name "unconnected-(U1-SDO{slash}SD0-Pad21)") (class "Default")
      (node (ref "U1") (pin "21") (pinfunction "SDO/SD0_21") (pintype "bidirectional"))
    )
    (net (code "198") (name "unconnected-(U1-SENSOR_VN-Pad5)") (class "Default")
      (node (ref "U1") (pin "5") (pinfunction "SENSOR_VN_5") (pintype "input"))
    )
    (net (code "199") (name "unconnected-(U1-SENSOR_VP-Pad4)") (class "Default")
      (node (ref "U1") (pin "4") (pinfunction "SENSOR_VP_4") (pintype "input"))
    )
    (net (code "200") (name "unconnected-(U1-SHD{slash}SD2-Pad17)") (class "Default")
      (node (ref "U1") (pin "17") (pinfunction "SHD/SD2_17") (pintype "bidirectional"))
    )
    (net (code "201") (name "unconnected-(U1-SWP{slash}SD3-Pad18)") (class "Default")
      (node (ref "U1") (pin "18") (pinfunction "SWP/SD3_18") (pintype "bidirectional"))
    )
  )
)
